# Motherboard.net
KiCad netlist of a schematic drawn in EAGLE
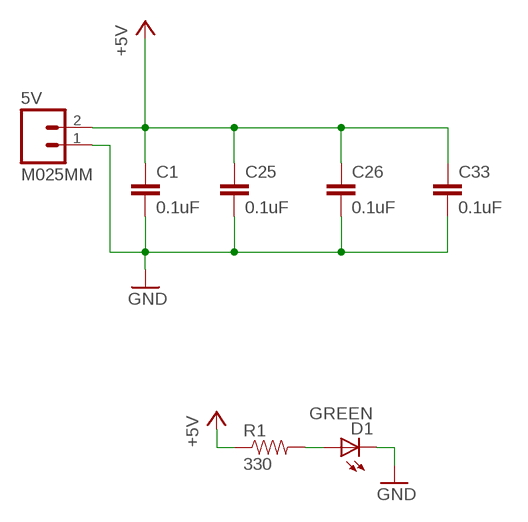
[diagram p0: schematic, sheet 1]
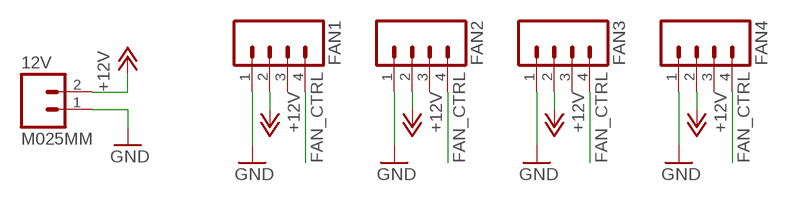
[diagram p1: schematic, sheet 2]
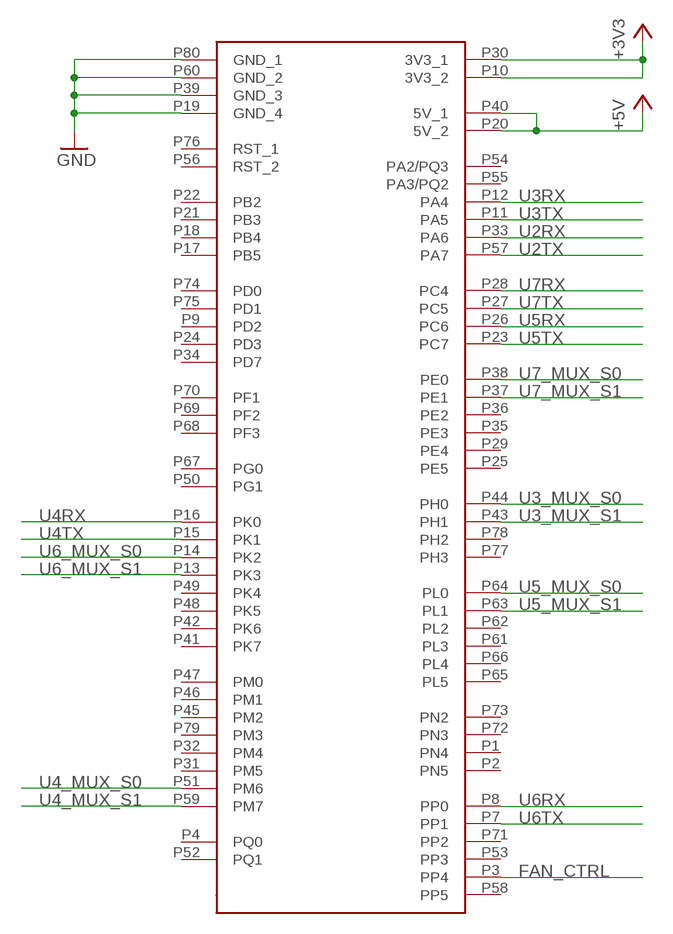
[diagram p2: schematic, sheet 3]
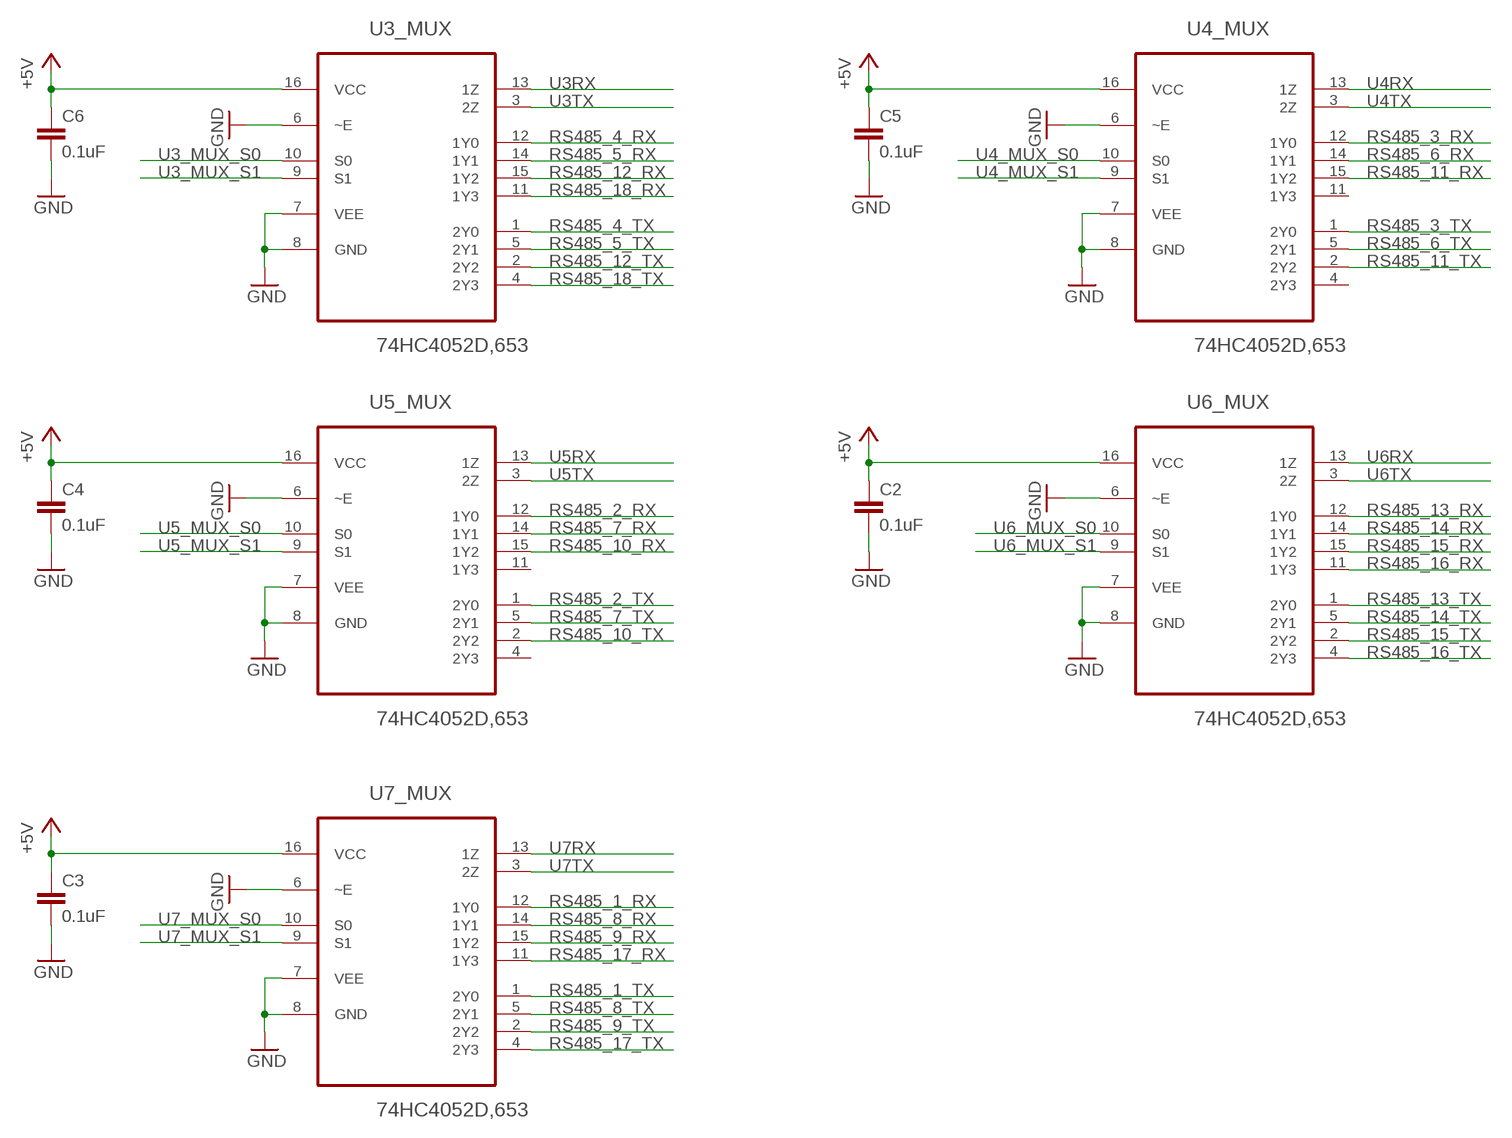
[diagram p3: schematic, sheet 4]
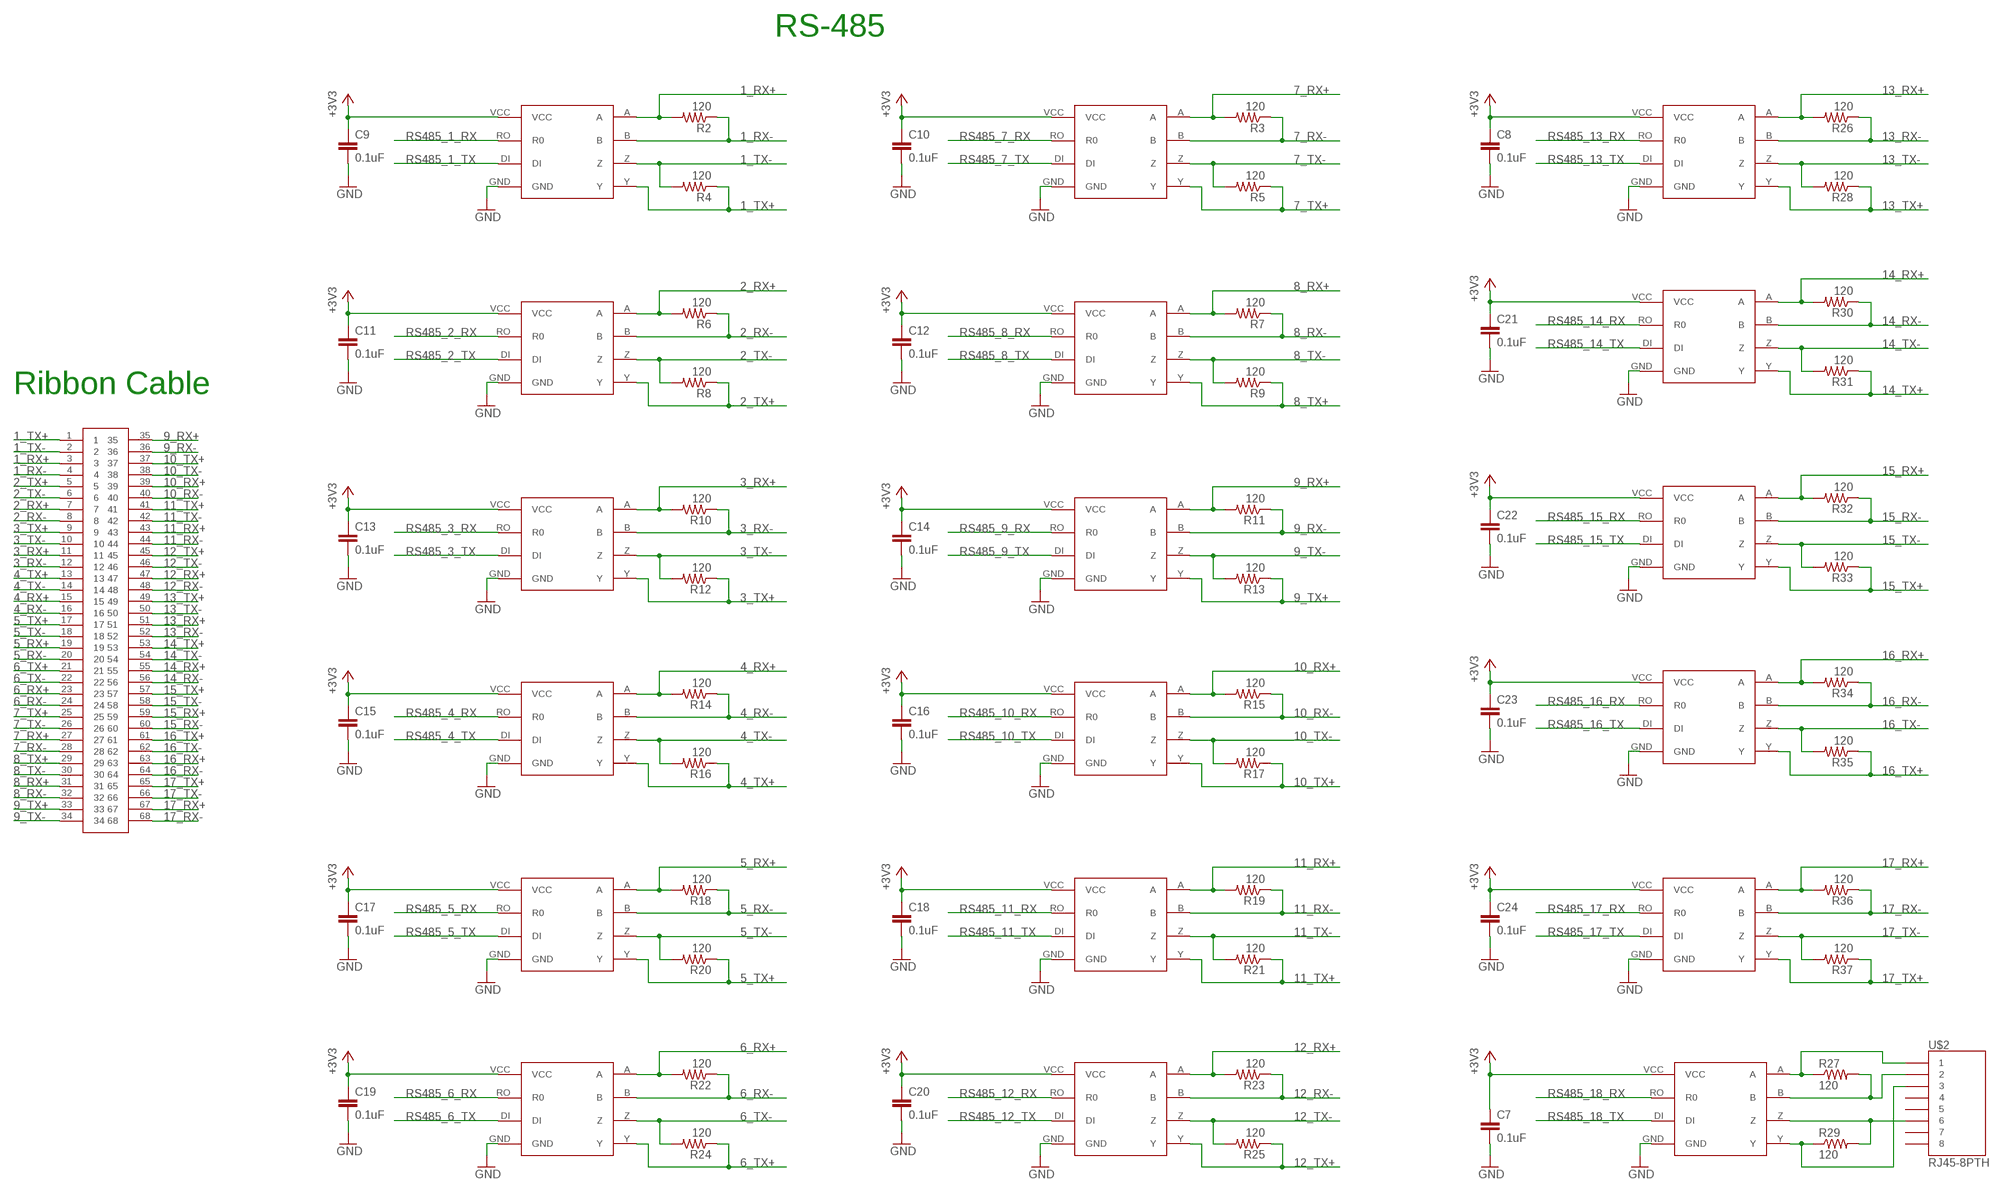
[diagram p4: schematic, sheet 5]
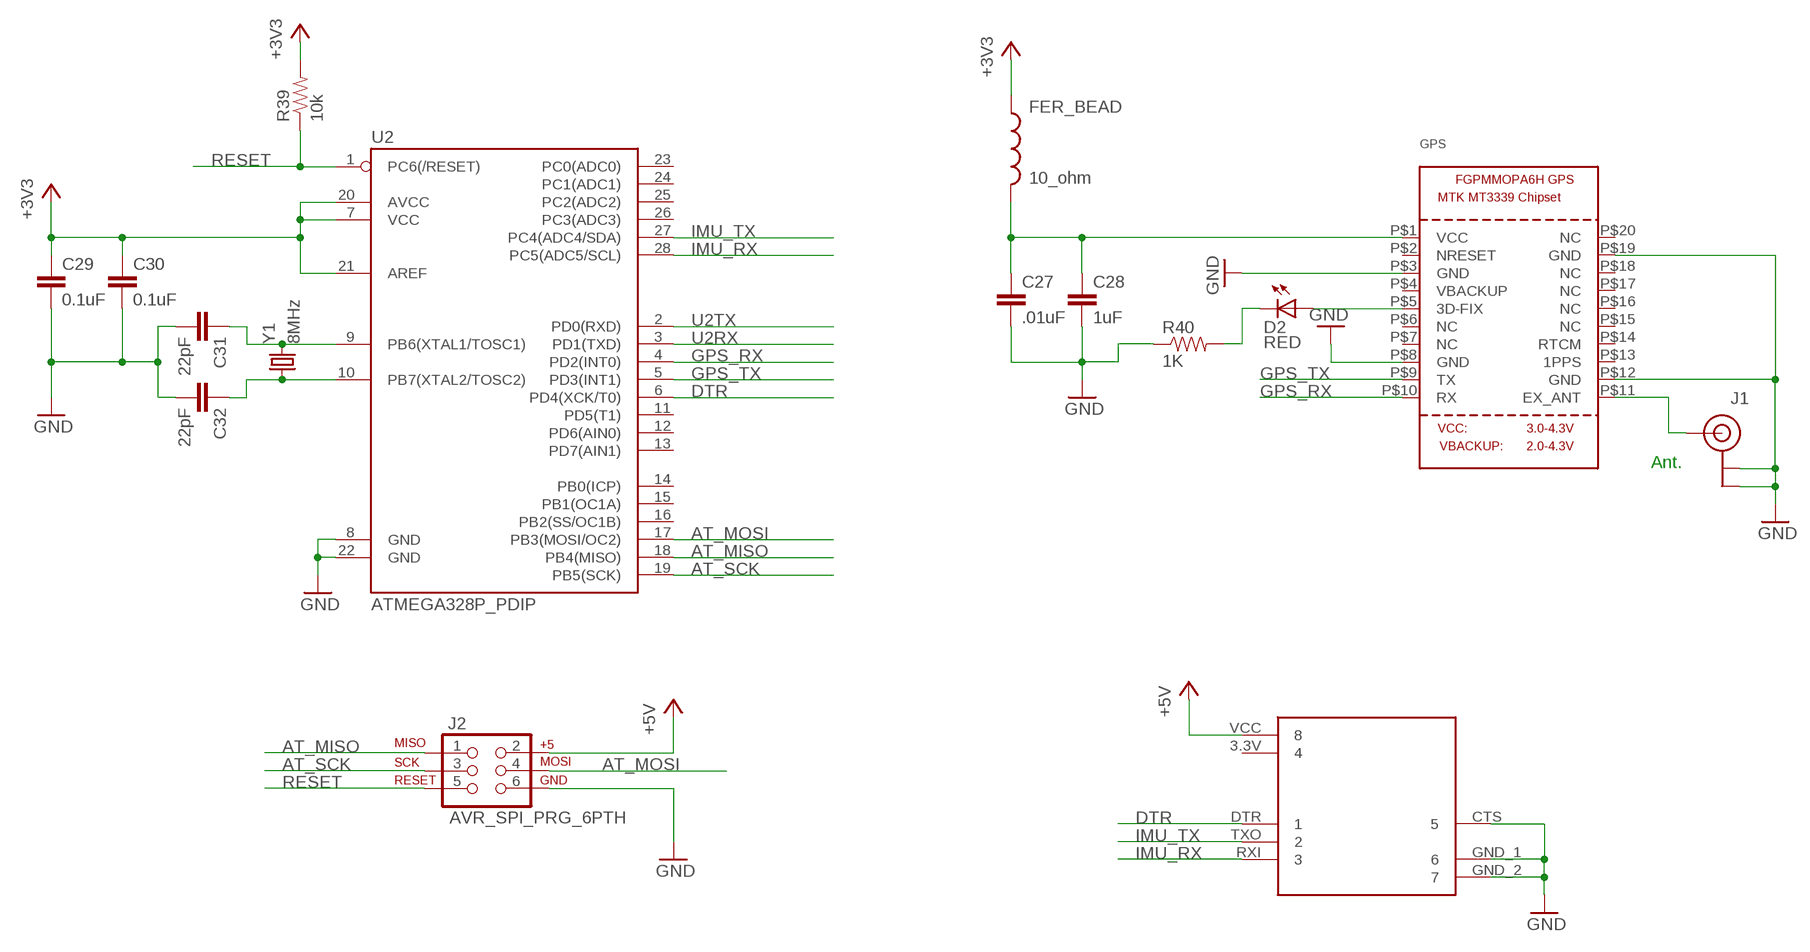
[diagram p5: schematic, sheet 6]
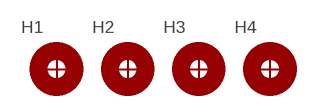
[diagram p6: schematic, sheet 7]

(export (version "E")
  (design (tool "Eeschema 10.0.6"))
  (components
    (comp (ref "C27")
      (value ".01uF")
      (footprint "eagle-import:1206")
      (libsource (lib "eagle-import") (part "CAP1206"))
    )
    (comp (ref "C28")
      (value "1uF")
      (footprint "eagle-import:1206")
      (libsource (lib "eagle-import") (part "CAP1206"))
    )
    (comp (ref "C29")
      (value "0.1uF")
      (footprint "eagle-import:1206")
      (libsource (lib "eagle-import") (part "CAP1206"))
    )
    (comp (ref "C30")
      (value "0.1uF")
      (footprint "eagle-import:1206")
      (libsource (lib "eagle-import") (part "CAP1206"))
    )
    (comp (ref "C31")
      (value "22pF")
      (footprint "eagle-import:1206")
      (libsource (lib "eagle-import") (part "CAP1206"))
    )
    (comp (ref "C32")
      (value "22pF")
      (footprint "eagle-import:1206")
      (libsource (lib "eagle-import") (part "CAP1206"))
    )
    (comp (ref "D2")
      (value "RED")
      (footprint "eagle-import:LED-1206")
      (libsource (lib "eagle-import") (part "LED-RED1206"))
    )
    (comp (ref "FER_BEAD")
      (value "10_ohm")
      (footprint "eagle-import:0603")
      (libsource (lib "eagle-import") (part "INDUCTOR30OHM,1.8A"))
    )
    (comp (ref "GPS")
      (value "GPS_FGPMMOPA6H")
      (footprint "eagle-import:FGPMMOPA6H")
      (libsource (lib "eagle-import") (part "GPS_FGPMMOPA6H"))
    )
    (comp (ref "J1")
      (value "U.FL")
      (footprint "eagle-import:U.FL")
      (libsource (lib "eagle-import") (part "U.FL"))
    )
    (comp (ref "J2")
      (value "AVR_SPI_PRG_6PTH")
      (footprint "eagle-import:2X3")
      (libsource (lib "eagle-import") (part "AVR_SPI_PRG_6PTH"))
    )
    (comp (ref "R39")
      (value "10k")
      (footprint "eagle-import:1206")
      (libsource (lib "eagle-import") (part "SparkFun-Resistors_RESISTOR1206"))
    )
    (comp (ref "R40")
      (value "1K")
      (footprint "eagle-import:1206")
      (libsource (lib "eagle-import") (part "RESISTOR1206"))
    )
    (comp (ref "U$1")
      (value "RAZOR_IMU")
      (footprint "eagle-import:RAZOR_IMU")
      (libsource (lib "eagle-import") (part "RAZOR_IMU"))
    )
    (comp (ref "U2")
      (value "ATMEGA328P_PDIP")
      (footprint "eagle-import:DIL28-3")
      (libsource (lib "eagle-import") (part "ATMEGA328P_PDIP"))
    )
    (comp (ref "Y1")
      (value "8MHz")
      (footprint "eagle-import:HC49US")
      (libsource (lib "eagle-import") (part "CRYSTALHC49US"))
    )
    (comp (ref "5V")
      (value "M025MM")
      (footprint "eagle-import:SCREWTERMINAL-5MM-2")
      (libsource (lib "eagle-import") (part "M025MM"))
    )
    (comp (ref "C1")
      (value "0.1uF")
      (footprint "eagle-import:1206")
      (libsource (lib "eagle-import") (part "CAP1206"))
    )
    (comp (ref "C25")
      (value "0.1uF")
      (footprint "eagle-import:1206")
      (libsource (lib "eagle-import") (part "CAP1206"))
    )
    (comp (ref "C26")
      (value "0.1uF")
      (footprint "eagle-import:1206")
      (libsource (lib "eagle-import") (part "CAP1206"))
    )
    (comp (ref "C33")
      (value "0.1uF")
      (footprint "eagle-import:1206")
      (libsource (lib "eagle-import") (part "CAP1206"))
    )
    (comp (ref "D1")
      (value "GREEN")
      (footprint "eagle-import:LED-1206")
      (libsource (lib "eagle-import") (part "LED-GREENLARGE"))
    )
    (comp (ref "R1")
      (value "330")
      (footprint "eagle-import:1206")
      (libsource (lib "eagle-import") (part "RESISTOR1206"))
    )
    (comp (ref "H1")
      (value "H_MNTHOLE_#4")
      (footprint "eagle-import:H_MNTHOLE_#4")
      (libsource (lib "eagle-import") (part "H_MNTHOLE_#4"))
    )
    (comp (ref "H2")
      (value "H_MNTHOLE_#4")
      (footprint "eagle-import:H_MNTHOLE_#4")
      (libsource (lib "eagle-import") (part "H_MNTHOLE_#4"))
    )
    (comp (ref "H3")
      (value "H_MNTHOLE_#4")
      (footprint "eagle-import:H_MNTHOLE_#4")
      (libsource (lib "eagle-import") (part "H_MNTHOLE_#4"))
    )
    (comp (ref "H4")
      (value "H_MNTHOLE_#4")
      (footprint "eagle-import:H_MNTHOLE_#4")
      (libsource (lib "eagle-import") (part "H_MNTHOLE_#4"))
    )
    (comp (ref "C2")
      (value "0.1uF")
      (footprint "eagle-import:1206")
      (libsource (lib "eagle-import") (part "CAP1206"))
    )
    (comp (ref "C3")
      (value "0.1uF")
      (footprint "eagle-import:1206")
      (libsource (lib "eagle-import") (part "CAP1206"))
    )
    (comp (ref "C4")
      (value "0.1uF")
      (footprint "eagle-import:1206")
      (libsource (lib "eagle-import") (part "CAP1206"))
    )
    (comp (ref "C5")
      (value "0.1uF")
      (footprint "eagle-import:1206")
      (libsource (lib "eagle-import") (part "CAP1206"))
    )
    (comp (ref "C6")
      (value "0.1uF")
      (footprint "eagle-import:1206")
      (libsource (lib "eagle-import") (part "CAP1206"))
    )
    (comp (ref "U3_MUX")
      (value "74HC4052D,653")
      (footprint "eagle-import:SOIC127P600X175-16N")
      (libsource (lib "eagle-import") (part "74HC4052D,653"))
    )
    (comp (ref "U4_MUX")
      (value "74HC4052D,653")
      (footprint "eagle-import:SOIC127P600X175-16N")
      (libsource (lib "eagle-import") (part "74HC4052D,653"))
    )
    (comp (ref "U5_MUX")
      (value "74HC4052D,653")
      (footprint "eagle-import:SOIC127P600X175-16N")
      (libsource (lib "eagle-import") (part "74HC4052D,653"))
    )
    (comp (ref "U6_MUX")
      (value "74HC4052D,653")
      (footprint "eagle-import:SOIC127P600X175-16N")
      (libsource (lib "eagle-import") (part "74HC4052D,653"))
    )
    (comp (ref "U7_MUX")
      (value "74HC4052D,653")
      (footprint "eagle-import:SOIC127P600X175-16N")
      (libsource (lib "eagle-import") (part "74HC4052D,653"))
    )
    (comp (ref "C7")
      (value "0.1uF")
      (footprint "eagle-import:1206")
      (libsource (lib "eagle-import") (part "CAP1206"))
    )
    (comp (ref "C8")
      (value "0.1uF")
      (footprint "eagle-import:1206")
      (libsource (lib "eagle-import") (part "CAP1206"))
    )
    (comp (ref "C9")
      (value "0.1uF")
      (footprint "eagle-import:1206")
      (libsource (lib "eagle-import") (part "CAP1206"))
    )
    (comp (ref "C10")
      (value "0.1uF")
      (footprint "eagle-import:1206")
      (libsource (lib "eagle-import") (part "CAP1206"))
    )
    (comp (ref "C11")
      (value "0.1uF")
      (footprint "eagle-import:1206")
      (libsource (lib "eagle-import") (part "CAP1206"))
    )
    (comp (ref "C12")
      (value "0.1uF")
      (footprint "eagle-import:1206")
      (libsource (lib "eagle-import") (part "CAP1206"))
    )
    (comp (ref "C13")
      (value "0.1uF")
      (footprint "eagle-import:1206")
      (libsource (lib "eagle-import") (part "CAP1206"))
    )
    (comp (ref "C14")
      (value "0.1uF")
      (footprint "eagle-import:1206")
      (libsource (lib "eagle-import") (part "CAP1206"))
    )
    (comp (ref "C15")
      (value "0.1uF")
      (footprint "eagle-import:1206")
      (libsource (lib "eagle-import") (part "CAP1206"))
    )
    (comp (ref "C16")
      (value "0.1uF")
      (footprint "eagle-import:1206")
      (libsource (lib "eagle-import") (part "CAP1206"))
    )
    (comp (ref "C17")
      (value "0.1uF")
      (footprint "eagle-import:1206")
      (libsource (lib "eagle-import") (part "CAP1206"))
    )
    (comp (ref "C18")
      (value "0.1uF")
      (footprint "eagle-import:1206")
      (libsource (lib "eagle-import") (part "CAP1206"))
    )
    (comp (ref "C19")
      (value "0.1uF")
      (footprint "eagle-import:1206")
      (libsource (lib "eagle-import") (part "CAP1206"))
    )
    (comp (ref "C20")
      (value "0.1uF")
      (footprint "eagle-import:1206")
      (libsource (lib "eagle-import") (part "CAP1206"))
    )
    (comp (ref "C21")
      (value "0.1uF")
      (footprint "eagle-import:1206")
      (libsource (lib "eagle-import") (part "CAP1206"))
    )
    (comp (ref "C22")
      (value "0.1uF")
      (footprint "eagle-import:1206")
      (libsource (lib "eagle-import") (part "CAP1206"))
    )
    (comp (ref "C23")
      (value "0.1uF")
      (footprint "eagle-import:1206")
      (libsource (lib "eagle-import") (part "CAP1206"))
    )
    (comp (ref "C24")
      (value "0.1uF")
      (footprint "eagle-import:1206")
      (libsource (lib "eagle-import") (part "CAP1206"))
    )
    (comp (ref "R2")
      (value "120")
      (footprint "eagle-import:1206")
      (libsource (lib "eagle-import") (part "RESISTOR1206"))
    )
    (comp (ref "R3")
      (value "120")
      (footprint "eagle-import:1206")
      (libsource (lib "eagle-import") (part "RESISTOR1206"))
    )
    (comp (ref "R4")
      (value "120")
      (footprint "eagle-import:1206")
      (libsource (lib "eagle-import") (part "RESISTOR1206"))
    )
    (comp (ref "R5")
      (value "120")
      (footprint "eagle-import:1206")
      (libsource (lib "eagle-import") (part "RESISTOR1206"))
    )
    (comp (ref "R6")
      (value "120")
      (footprint "eagle-import:1206")
      (libsource (lib "eagle-import") (part "RESISTOR1206"))
    )
    (comp (ref "R7")
      (value "120")
      (footprint "eagle-import:1206")
      (libsource (lib "eagle-import") (part "RESISTOR1206"))
    )
    (comp (ref "R8")
      (value "120")
      (footprint "eagle-import:1206")
      (libsource (lib "eagle-import") (part "RESISTOR1206"))
    )
    (comp (ref "R9")
      (value "120")
      (footprint "eagle-import:1206")
      (libsource (lib "eagle-import") (part "RESISTOR1206"))
    )
    (comp (ref "R10")
      (value "120")
      (footprint "eagle-import:1206")
      (libsource (lib "eagle-import") (part "RESISTOR1206"))
    )
    (comp (ref "R11")
      (value "120")
      (footprint "eagle-import:1206")
      (libsource (lib "eagle-import") (part "RESISTOR1206"))
    )
    (comp (ref "R12")
      (value "120")
      (footprint "eagle-import:1206")
      (libsource (lib "eagle-import") (part "RESISTOR1206"))
    )
    (comp (ref "R13")
      (value "120")
      (footprint "eagle-import:1206")
      (libsource (lib "eagle-import") (part "RESISTOR1206"))
    )
    (comp (ref "R14")
      (value "120")
      (footprint "eagle-import:1206")
      (libsource (lib "eagle-import") (part "RESISTOR1206"))
    )
    (comp (ref "R15")
      (value "120")
      (footprint "eagle-import:1206")
      (libsource (lib "eagle-import") (part "RESISTOR1206"))
    )
    (comp (ref "R16")
      (value "120")
      (footprint "eagle-import:1206")
      (libsource (lib "eagle-import") (part "RESISTOR1206"))
    )
    (comp (ref "R17")
      (value "120")
      (footprint "eagle-import:1206")
      (libsource (lib "eagle-import") (part "RESISTOR1206"))
    )
    (comp (ref "R18")
      (value "120")
      (footprint "eagle-import:1206")
      (libsource (lib "eagle-import") (part "RESISTOR1206"))
    )
    (comp (ref "R19")
      (value "120")
      (footprint "eagle-import:1206")
      (libsource (lib "eagle-import") (part "RESISTOR1206"))
    )
    (comp (ref "R20")
      (value "120")
      (footprint "eagle-import:1206")
      (libsource (lib "eagle-import") (part "RESISTOR1206"))
    )
    (comp (ref "R21")
      (value "120")
      (footprint "eagle-import:1206")
      (libsource (lib "eagle-import") (part "RESISTOR1206"))
    )
    (comp (ref "R22")
      (value "120")
      (footprint "eagle-import:1206")
      (libsource (lib "eagle-import") (part "RESISTOR1206"))
    )
    (comp (ref "R23")
      (value "120")
      (footprint "eagle-import:1206")
      (libsource (lib "eagle-import") (part "RESISTOR1206"))
    )
    (comp (ref "R24")
      (value "120")
      (footprint "eagle-import:1206")
      (libsource (lib "eagle-import") (part "RESISTOR1206"))
    )
    (comp (ref "R25")
      (value "120")
      (footprint "eagle-import:1206")
      (libsource (lib "eagle-import") (part "RESISTOR1206"))
    )
    (comp (ref "R26")
      (value "120")
      (footprint "eagle-import:1206")
      (libsource (lib "eagle-import") (part "RESISTOR1206"))
    )
    (comp (ref "R27")
      (value "120")
      (footprint "eagle-import:1206")
      (libsource (lib "eagle-import") (part "RESISTOR1206"))
    )
    (comp (ref "R28")
      (value "120")
      (footprint "eagle-import:1206")
      (libsource (lib "eagle-import") (part "RESISTOR1206"))
    )
    (comp (ref "R29")
      (value "120")
      (footprint "eagle-import:1206")
      (libsource (lib "eagle-import") (part "RESISTOR1206"))
    )
    (comp (ref "R30")
      (value "120")
      (footprint "eagle-import:1206")
      (libsource (lib "eagle-import") (part "RESISTOR1206"))
    )
    (comp (ref "R31")
      (value "120")
      (footprint "eagle-import:1206")
      (libsource (lib "eagle-import") (part "RESISTOR1206"))
    )
    (comp (ref "R32")
      (value "120")
      (footprint "eagle-import:1206")
      (libsource (lib "eagle-import") (part "RESISTOR1206"))
    )
    (comp (ref "R33")
      (value "120")
      (footprint "eagle-import:1206")
      (libsource (lib "eagle-import") (part "RESISTOR1206"))
    )
    (comp (ref "R34")
      (value "120")
      (footprint "eagle-import:1206")
      (libsource (lib "eagle-import") (part "RESISTOR1206"))
    )
    (comp (ref "R35")
      (value "120")
      (footprint "eagle-import:1206")
      (libsource (lib "eagle-import") (part "RESISTOR1206"))
    )
    (comp (ref "R36")
      (value "120")
      (footprint "eagle-import:1206")
      (libsource (lib "eagle-import") (part "RESISTOR1206"))
    )
    (comp (ref "R37")
      (value "120")
      (footprint "eagle-import:1206")
      (libsource (lib "eagle-import") (part "RESISTOR1206"))
    )
    (comp (ref "RS-485-2")
      (value "MAX3077")
      (footprint "eagle-import:MAX3070E")
      (libsource (lib "eagle-import") (part "MAX3077"))
    )
    (comp (ref "RS_TRANS_1")
      (value "MAX3077")
      (footprint "eagle-import:MAX3070E")
      (libsource (lib "eagle-import") (part "MAX3077"))
    )
    (comp (ref "RS_TRANS_2")
      (value "MAX3077")
      (footprint "eagle-import:MAX3070E")
      (libsource (lib "eagle-import") (part "MAX3077"))
    )
    (comp (ref "RS_TRANS_3")
      (value "MAX3077")
      (footprint "eagle-import:MAX3070E")
      (libsource (lib "eagle-import") (part "MAX3077"))
    )
    (comp (ref "RS_TRANS_4")
      (value "MAX3077")
      (footprint "eagle-import:MAX3070E")
      (libsource (lib "eagle-import") (part "MAX3077"))
    )
    (comp (ref "RS_TRANS_5")
      (value "MAX3077")
      (footprint "eagle-import:MAX3070E")
      (libsource (lib "eagle-import") (part "MAX3077"))
    )
    (comp (ref "RS_TRANS_6")
      (value "MAX3077")
      (footprint "eagle-import:MAX3070E")
      (libsource (lib "eagle-import") (part "MAX3077"))
    )
    (comp (ref "RS_TRANS_7")
      (value "MAX3077")
      (footprint "eagle-import:MAX3070E")
      (libsource (lib "eagle-import") (part "MAX3077"))
    )
    (comp (ref "RS_TRANS_8")
      (value "MAX3077")
      (footprint "eagle-import:MAX3070E")
      (libsource (lib "eagle-import") (part "MAX3077"))
    )
    (comp (ref "RS_TRANS_9")
      (value "MAX3077")
      (footprint "eagle-import:MAX3070E")
      (libsource (lib "eagle-import") (part "MAX3077"))
    )
    (comp (ref "RS_TRANS_10")
      (value "MAX3077")
      (footprint "eagle-import:MAX3070E")
      (libsource (lib "eagle-import") (part "MAX3077"))
    )
    (comp (ref "RS_TRANS_11")
      (value "MAX3077")
      (footprint "eagle-import:MAX3070E")
      (libsource (lib "eagle-import") (part "MAX3077"))
    )
    (comp (ref "RS_TRANS_12")
      (value "MAX3077")
      (footprint "eagle-import:MAX3070E")
      (libsource (lib "eagle-import") (part "MAX3077"))
    )
    (comp (ref "RS_TRANS_13")
      (value "MAX3077")
      (footprint "eagle-import:MAX3070E")
      (libsource (lib "eagle-import") (part "MAX3077"))
    )
    (comp (ref "RS_TRANS_14")
      (value "MAX3077")
      (footprint "eagle-import:MAX3070E")
      (libsource (lib "eagle-import") (part "MAX3077"))
    )
    (comp (ref "RS_TRANS_15")
      (value "MAX3077")
      (footprint "eagle-import:MAX3070E")
      (libsource (lib "eagle-import") (part "MAX3077"))
    )
    (comp (ref "RS_TRANS_16")
      (value "MAX3077")
      (footprint "eagle-import:MAX3070E")
      (libsource (lib "eagle-import") (part "MAX3077"))
    )
    (comp (ref "RS_TRANS_17")
      (value "MAX3077")
      (footprint "eagle-import:MAX3070E")
      (libsource (lib "eagle-import") (part "MAX3077"))
    )
    (comp (ref "U$2")
      (value "RJ45-8PTH")
      (footprint "eagle-import:RJ45-8")
      (libsource (lib "eagle-import") (part "RJ45-8PTH"))
    )
    (comp (ref "U$4")
      (value "TB60050685100")
      (footprint "eagle-import:60050685100")
      (libsource (lib "eagle-import") (part "TB60050685100"))
    )
    (comp (ref "12V")
      (value "M025MM")
      (footprint "eagle-import:SCREWTERMINAL-5MM-2")
      (libsource (lib "eagle-import") (part "M025MM"))
    )
    (comp (ref "FAN1")
      (value "M04LONGPADS")
      (footprint "eagle-import:1X04_LONGPADS")
      (libsource (lib "eagle-import") (part "M04LONGPADS"))
    )
    (comp (ref "FAN2")
      (value "M04LONGPADS")
      (footprint "eagle-import:1X04_LONGPADS")
      (libsource (lib "eagle-import") (part "M04LONGPADS"))
    )
    (comp (ref "FAN3")
      (value "M04LONGPADS")
      (footprint "eagle-import:1X04_LONGPADS")
      (libsource (lib "eagle-import") (part "M04LONGPADS"))
    )
    (comp (ref "FAN4")
      (value "M04LONGPADS")
      (footprint "eagle-import:1X04_LONGPADS")
      (libsource (lib "eagle-import") (part "M04LONGPADS"))
    )
    (comp (ref "U$5")
      (value "STELLARISLAUNCHPAD_CONNECTED")
      (footprint "eagle-import:STELLARISLAUNCHPAD_CONNECTED")
      (libsource (lib "eagle-import") (part "STELLARISLAUNCHPAD_CONNECTED"))
    )
  )
  (nets
    (net (code "1") (name "+3V3") (class "Default")
      (node (ref "C10") (pin "1") (pinfunction "1_1") (pintype "passive"))
      (node (ref "C11") (pin "1") (pinfunction "1_1") (pintype "passive"))
      (node (ref "C12") (pin "1") (pinfunction "1_1") (pintype "passive"))
      (node (ref "C13") (pin "1") (pinfunction "1_1") (pintype "passive"))
      (node (ref "C14") (pin "1") (pinfunction "1_1") (pintype "passive"))
      (node (ref "C15") (pin "1") (pinfunction "1_1") (pintype "passive"))
      (node (ref "C16") (pin "1") (pinfunction "1_1") (pintype "passive"))
      (node (ref "C17") (pin "1") (pinfunction "1_1") (pintype "passive"))
      (node (ref "C18") (pin "1") (pinfunction "1_1") (pintype "passive"))
      (node (ref "C19") (pin "1") (pinfunction "1_1") (pintype "passive"))
      (node (ref "C20") (pin "1") (pinfunction "1_1") (pintype "passive"))
      (node (ref "C21") (pin "1") (pinfunction "1_1") (pintype "passive"))
      (node (ref "C22") (pin "1") (pinfunction "1_1") (pintype "passive"))
      (node (ref "C23") (pin "1") (pinfunction "1_1") (pintype "passive"))
      (node (ref "C24") (pin "1") (pinfunction "1_1") (pintype "passive"))
      (node (ref "C29") (pin "1") (pinfunction "1_1") (pintype "passive"))
      (node (ref "C30") (pin "1") (pinfunction "1_1") (pintype "passive"))
      (node (ref "C7") (pin "1") (pinfunction "1_1") (pintype "passive"))
      (node (ref "C8") (pin "1") (pinfunction "1_1") (pintype "passive"))
      (node (ref "C9") (pin "1") (pinfunction "1_1") (pintype "passive"))
      (node (ref "FER_BEAD") (pin "1") (pinfunction "1_1") (pintype "passive"))
      (node (ref "R39") (pin "2") (pinfunction "2_2") (pintype "passive"))
      (node (ref "RS-485-2") (pin "VCC") (pinfunction "VCC_VCC") (pintype "bidirectional"))
      (node (ref "RS_TRANS_1") (pin "VCC") (pinfunction "VCC_VCC") (pintype "bidirectional"))
      (node (ref "RS_TRANS_10") (pin "VCC") (pinfunction "VCC_VCC") (pintype "bidirectional"))
      (node (ref "RS_TRANS_11") (pin "VCC") (pinfunction "VCC_VCC") (pintype "bidirectional"))
      (node (ref "RS_TRANS_12") (pin "VCC") (pinfunction "VCC_VCC") (pintype "bidirectional"))
      (node (ref "RS_TRANS_13") (pin "VCC") (pinfunction "VCC_VCC") (pintype "bidirectional"))
      (node (ref "RS_TRANS_14") (pin "VCC") (pinfunction "VCC_VCC") (pintype "bidirectional"))
      (node (ref "RS_TRANS_15") (pin "VCC") (pinfunction "VCC_VCC") (pintype "bidirectional"))
      (node (ref "RS_TRANS_16") (pin "VCC") (pinfunction "VCC_VCC") (pintype "bidirectional"))
      (node (ref "RS_TRANS_17") (pin "VCC") (pinfunction "VCC_VCC") (pintype "bidirectional"))
      (node (ref "RS_TRANS_2") (pin "VCC") (pinfunction "VCC_VCC") (pintype "bidirectional"))
      (node (ref "RS_TRANS_3") (pin "VCC") (pinfunction "VCC_VCC") (pintype "bidirectional"))
      (node (ref "RS_TRANS_4") (pin "VCC") (pinfunction "VCC_VCC") (pintype "bidirectional"))
      (node (ref "RS_TRANS_5") (pin "VCC") (pinfunction "VCC_VCC") (pintype "bidirectional"))
      (node (ref "RS_TRANS_6") (pin "VCC") (pinfunction "VCC_VCC") (pintype "bidirectional"))
      (node (ref "RS_TRANS_7") (pin "VCC") (pinfunction "VCC_VCC") (pintype "bidirectional"))
      (node (ref "RS_TRANS_8") (pin "VCC") (pinfunction "VCC_VCC") (pintype "bidirectional"))
      (node (ref "RS_TRANS_9") (pin "VCC") (pinfunction "VCC_VCC") (pintype "bidirectional"))
      (node (ref "U$5") (pin "P10") (pinfunction "3V3_2_P10") (pintype "bidirectional"))
      (node (ref "U$5") (pin "P30") (pinfunction "3V3_1_P30") (pintype "bidirectional"))
      (node (ref "U2") (pin "20") (pinfunction "AVCC_20") (pintype "bidirectional"))
      (node (ref "U2") (pin "21") (pinfunction "AREF_21") (pintype "bidirectional"))
      (node (ref "U2") (pin "7") (pinfunction "VCC_7") (pintype "bidirectional"))
    )
    (net (code "2") (name "+5V") (class "Default")
      (node (ref "5V") (pin "2") (pinfunction "2_2") (pintype "passive"))
      (node (ref "C1") (pin "1") (pinfunction "1_1") (pintype "passive"))
      (node (ref "C2") (pin "1") (pinfunction "1_1") (pintype "passive"))
      (node (ref "C25") (pin "1") (pinfunction "1_1") (pintype "passive"))
      (node (ref "C26") (pin "1") (pinfunction "1_1") (pintype "passive"))
      (node (ref "C3") (pin "1") (pinfunction "1_1") (pintype "passive"))
      (node (ref "C33") (pin "1") (pinfunction "1_1") (pintype "passive"))
      (node (ref "C4") (pin "1") (pinfunction "1_1") (pintype "passive"))
      (node (ref "C5") (pin "1") (pinfunction "1_1") (pintype "passive"))
      (node (ref "C6") (pin "1") (pinfunction "1_1") (pintype "passive"))
      (node (ref "J2") (pin "2") (pinfunction "2_2") (pintype "passive"))
      (node (ref "R1") (pin "1") (pinfunction "1_1") (pintype "passive"))
      (node (ref "U$1") (pin "VCC") (pinfunction "8_VCC") (pintype "bidirectional"))
      (node (ref "U$5") (pin "P20") (pinfunction "5V_2_P20") (pintype "bidirectional"))
      (node (ref "U$5") (pin "P40") (pinfunction "5V_1_P40") (pintype "bidirectional"))
      (node (ref "U3_MUX") (pin "16") (pinfunction "VCC_16") (pintype "power_in"))
      (node (ref "U4_MUX") (pin "16") (pinfunction "VCC_16") (pintype "power_in"))
      (node (ref "U5_MUX") (pin "16") (pinfunction "VCC_16") (pintype "power_in"))
      (node (ref "U6_MUX") (pin "16") (pinfunction "VCC_16") (pintype "power_in"))
      (node (ref "U7_MUX") (pin "16") (pinfunction "VCC_16") (pintype "power_in"))
    )
    (net (code "3") (name "+12V") (class "Default")
      (node (ref "12V") (pin "2") (pinfunction "2_2") (pintype "passive"))
      (node (ref "FAN1") (pin "2") (pinfunction "2_2") (pintype "passive"))
      (node (ref "FAN2") (pin "2") (pinfunction "2_2") (pintype "passive"))
      (node (ref "FAN3") (pin "2") (pinfunction "2_2") (pintype "passive"))
      (node (ref "FAN4") (pin "2") (pinfunction "2_2") (pintype "passive"))
    )
    (net (code "4") (name "1_RX+") (class "Default")
      (node (ref "R2") (pin "2") (pinfunction "2_2") (pintype "passive"))
      (node (ref "RS_TRANS_1") (pin "A") (pinfunction "A_A") (pintype "bidirectional"))
      (node (ref "U$4") (pin "3") (pinfunction "3_3") (pintype "bidirectional"))
    )
    (net (code "5") (name "1_RX-") (class "Default")
      (node (ref "R2") (pin "1") (pinfunction "1_1") (pintype "passive"))
      (node (ref "RS_TRANS_1") (pin "B") (pinfunction "B_B") (pintype "bidirectional"))
      (node (ref "U$4") (pin "4") (pinfunction "4_4") (pintype "bidirectional"))
    )
    (net (code "6") (name "1_TX+") (class "Default")
      (node (ref "R4") (pin "1") (pinfunction "1_1") (pintype "passive"))
      (node (ref "RS_TRANS_1") (pin "Y") (pinfunction "Y_Y") (pintype "bidirectional"))
      (node (ref "U$4") (pin "1") (pinfunction "1_1") (pintype "bidirectional"))
    )
    (net (code "7") (name "1_TX-") (class "Default")
      (node (ref "R4") (pin "2") (pinfunction "2_2") (pintype "passive"))
      (node (ref "RS_TRANS_1") (pin "Z") (pinfunction "Z_Z") (pintype "bidirectional"))
      (node (ref "U$4") (pin "2") (pinfunction "2_2") (pintype "bidirectional"))
    )
    (net (code "8") (name "2_RX+") (class "Default")
      (node (ref "R6") (pin "2") (pinfunction "2_2") (pintype "passive"))
      (node (ref "RS_TRANS_3") (pin "A") (pinfunction "A_A") (pintype "bidirectional"))
      (node (ref "U$4") (pin "7") (pinfunction "7_7") (pintype "bidirectional"))
    )
    (net (code "9") (name "2_RX-") (class "Default")
      (node (ref "R6") (pin "1") (pinfunction "1_1") (pintype "passive"))
      (node (ref "RS_TRANS_3") (pin "B") (pinfunction "B_B") (pintype "bidirectional"))
      (node (ref "U$4") (pin "8") (pinfunction "8_8") (pintype "bidirectional"))
    )
    (net (code "10") (name "2_TX+") (class "Default")
      (node (ref "R8") (pin "1") (pinfunction "1_1") (pintype "passive"))
      (node (ref "RS_TRANS_3") (pin "Y") (pinfunction "Y_Y") (pintype "bidirectional"))
      (node (ref "U$4") (pin "5") (pinfunction "5_5") (pintype "bidirectional"))
    )
    (net (code "11") (name "2_TX-") (class "Default")
      (node (ref "R8") (pin "2") (pinfunction "2_2") (pintype "passive"))
      (node (ref "RS_TRANS_3") (pin "Z") (pinfunction "Z_Z") (pintype "bidirectional"))
      (node (ref "U$4") (pin "6") (pinfunction "6_6") (pintype "bidirectional"))
    )
    (net (code "12") (name "3_RX+") (class "Default")
      (node (ref "R10") (pin "2") (pinfunction "2_2") (pintype "passive"))
      (node (ref "RS_TRANS_5") (pin "A") (pinfunction "A_A") (pintype "bidirectional"))
      (node (ref "U$4") (pin "11") (pinfunction "11_11") (pintype "bidirectional"))
    )
    (net (code "13") (name "3_RX-") (class "Default")
      (node (ref "R10") (pin "1") (pinfunction "1_1") (pintype "passive"))
      (node (ref "RS_TRANS_5") (pin "B") (pinfunction "B_B") (pintype "bidirectional"))
      (node (ref "U$4") (pin "12") (pinfunction "12_12") (pintype "bidirectional"))
    )
    (net (code "14") (name "3_TX+") (class "Default")
      (node (ref "R12") (pin "1") (pinfunction "1_1") (pintype "passive"))
      (node (ref "RS_TRANS_5") (pin "Y") (pinfunction "Y_Y") (pintype "bidirectional"))
      (node (ref "U$4") (pin "9") (pinfunction "9_9") (pintype "bidirectional"))
    )
    (net (code "15") (name "3_TX-") (class "Default")
      (node (ref "R12") (pin "2") (pinfunction "2_2") (pintype "passive"))
      (node (ref "RS_TRANS_5") (pin "Z") (pinfunction "Z_Z") (pintype "bidirectional"))
      (node (ref "U$4") (pin "10") (pinfunction "10_10") (pintype "bidirectional"))
    )
    (net (code "16") (name "4_RX+") (class "Default")
      (node (ref "R14") (pin "2") (pinfunction "2_2") (pintype "passive"))
      (node (ref "RS_TRANS_7") (pin "A") (pinfunction "A_A") (pintype "bidirectional"))
      (node (ref "U$4") (pin "15") (pinfunction "15_15") (pintype "bidirectional"))
    )
    (net (code "17") (name "4_RX-") (class "Default")
      (node (ref "R14") (pin "1") (pinfunction "1_1") (pintype "passive"))
      (node (ref "RS_TRANS_7") (pin "B") (pinfunction "B_B") (pintype "bidirectional"))
      (node (ref "U$4") (pin "16") (pinfunction "16_16") (pintype "bidirectional"))
    )
    (net (code "18") (name "4_TX+") (class "Default")
      (node (ref "R16") (pin "1") (pinfunction "1_1") (pintype "passive"))
      (node (ref "RS_TRANS_7") (pin "Y") (pinfunction "Y_Y") (pintype "bidirectional"))
      (node (ref "U$4") (pin "13") (pinfunction "13_13") (pintype "bidirectional"))
    )
    (net (code "19") (name "4_TX-") (class "Default")
      (node (ref "R16") (pin "2") (pinfunction "2_2") (pintype "passive"))
      (node (ref "RS_TRANS_7") (pin "Z") (pinfunction "Z_Z") (pintype "bidirectional"))
      (node (ref "U$4") (pin "14") (pinfunction "14_14") (pintype "bidirectional"))
    )
    (net (code "20") (name "5_RX+") (class "Default")
      (node (ref "R18") (pin "2") (pinfunction "2_2") (pintype "passive"))
      (node (ref "RS_TRANS_9") (pin "A") (pinfunction "A_A") (pintype "bidirectional"))
      (node (ref "U$4") (pin "19") (pinfunction "19_19") (pintype "bidirectional"))
    )
    (net (code "21") (name "5_RX-") (class "Default")
      (node (ref "R18") (pin "1") (pinfunction "1_1") (pintype "passive"))
      (node (ref "RS_TRANS_9") (pin "B") (pinfunction "B_B") (pintype "bidirectional"))
      (node (ref "U$4") (pin "20") (pinfunction "20_20") (pintype "bidirectional"))
    )
    (net (code "22") (name "5_TX+") (class "Default")
      (node (ref "R20") (pin "1") (pinfunction "1_1") (pintype "passive"))
      (node (ref "RS_TRANS_9") (pin "Y") (pinfunction "Y_Y") (pintype "bidirectional"))
      (node (ref "U$4") (pin "17") (pinfunction "17_17") (pintype "bidirectional"))
    )
    (net (code "23") (name "5_TX-") (class "Default")
      (node (ref "R20") (pin "2") (pinfunction "2_2") (pintype "passive"))
      (node (ref "RS_TRANS_9") (pin "Z") (pinfunction "Z_Z") (pintype "bidirectional"))
      (node (ref "U$4") (pin "18") (pinfunction "18_18") (pintype "bidirectional"))
    )
    (net (code "24") (name "6_RX+") (class "Default")
      (node (ref "R22") (pin "2") (pinfunction "2_2") (pintype "passive"))
      (node (ref "RS_TRANS_11") (pin "A") (pinfunction "A_A") (pintype "bidirectional"))
      (node (ref "U$4") (pin "23") (pinfunction "23_23") (pintype "bidirectional"))
    )
    (net (code "25") (name "6_RX-") (class "Default")
      (node (ref "R22") (pin "1") (pinfunction "1_1") (pintype "passive"))
      (node (ref "RS_TRANS_11") (pin "B") (pinfunction "B_B") (pintype "bidirectional"))
      (node (ref "U$4") (pin "24") (pinfunction "24_24") (pintype "bidirectional"))
    )
    (net (code "26") (name "6_TX+") (class "Default")
      (node (ref "R24") (pin "1") (pinfunction "1_1") (pintype "passive"))
      (node (ref "RS_TRANS_11") (pin "Y") (pinfunction "Y_Y") (pintype "bidirectional"))
      (node (ref "U$4") (pin "21") (pinfunction "21_21") (pintype "bidirectional"))
    )
    (net (code "27") (name "6_TX-") (class "Default")
      (node (ref "R24") (pin "2") (pinfunction "2_2") (pintype "passive"))
      (node (ref "RS_TRANS_11") (pin "Z") (pinfunction "Z_Z") (pintype "bidirectional"))
      (node (ref "U$4") (pin "22") (pinfunction "22_22") (pintype "bidirectional"))
    )
    (net (code "28") (name "7_RX+") (class "Default")
      (node (ref "R3") (pin "2") (pinfunction "2_2") (pintype "passive"))
      (node (ref "RS_TRANS_2") (pin "A") (pinfunction "A_A") (pintype "bidirectional"))
      (node (ref "U$4") (pin "27") (pinfunction "27_27") (pintype "bidirectional"))
    )
    (net (code "29") (name "7_RX-") (class "Default")
      (node (ref "R3") (pin "1") (pinfunction "1_1") (pintype "passive"))
      (node (ref "RS_TRANS_2") (pin "B") (pinfunction "B_B") (pintype "bidirectional"))
      (node (ref "U$4") (pin "28") (pinfunction "28_28") (pintype "bidirectional"))
    )
    (net (code "30") (name "7_TX+") (class "Default")
      (node (ref "R5") (pin "1") (pinfunction "1_1") (pintype "passive"))
      (node (ref "RS_TRANS_2") (pin "Y") (pinfunction "Y_Y") (pintype "bidirectional"))
      (node (ref "U$4") (pin "25") (pinfunction "25_25") (pintype "bidirectional"))
    )
    (net (code "31") (name "7_TX-") (class "Default")
      (node (ref "R5") (pin "2") (pinfunction "2_2") (pintype "passive"))
      (node (ref "RS_TRANS_2") (pin "Z") (pinfunction "Z_Z") (pintype "bidirectional"))
      (node (ref "U$4") (pin "26") (pinfunction "26_26") (pintype "bidirectional"))
    )
    (net (code "32") (name "8_RX+") (class "Default")
      (node (ref "R7") (pin "2") (pinfunction "2_2") (pintype "passive"))
      (node (ref "RS_TRANS_4") (pin "A") (pinfunction "A_A") (pintype "bidirectional"))
      (node (ref "U$4") (pin "31") (pinfunction "31_31") (pintype "bidirectional"))
    )
    (net (code "33") (name "8_RX-") (class "Default")
      (node (ref "R7") (pin "1") (pinfunction "1_1") (pintype "passive"))
      (node (ref "RS_TRANS_4") (pin "B") (pinfunction "B_B") (pintype "bidirectional"))
      (node (ref "U$4") (pin "32") (pinfunction "32_32") (pintype "bidirectional"))
    )
    (net (code "34") (name "8_TX+") (class "Default")
      (node (ref "R9") (pin "1") (pinfunction "1_1") (pintype "passive"))
      (node (ref "RS_TRANS_4") (pin "Y") (pinfunction "Y_Y") (pintype "bidirectional"))
      (node (ref "U$4") (pin "29") (pinfunction "29_29") (pintype "bidirectional"))
    )
    (net (code "35") (name "8_TX-") (class "Default")
      (node (ref "R9") (pin "2") (pinfunction "2_2") (pintype "passive"))
      (node (ref "RS_TRANS_4") (pin "Z") (pinfunction "Z_Z") (pintype "bidirectional"))
      (node (ref "U$4") (pin "30") (pinfunction "30_30") (pintype "bidirectional"))
    )
    (net (code "36") (name "9_RX+") (class "Default")
      (node (ref "R11") (pin "2") (pinfunction "2_2") (pintype "passive"))
      (node (ref "RS_TRANS_6") (pin "A") (pinfunction "A_A") (pintype "bidirectional"))
      (node (ref "U$4") (pin "35") (pinfunction "35_35") (pintype "bidirectional"))
    )
    (net (code "37") (name "9_RX-") (class "Default")
      (node (ref "R11") (pin "1") (pinfunction "1_1") (pintype "passive"))
      (node (ref "RS_TRANS_6") (pin "B") (pinfunction "B_B") (pintype "bidirectional"))
      (node (ref "U$4") (pin "36") (pinfunction "36_36") (pintype "bidirectional"))
    )
    (net (code "38") (name "9_TX+") (class "Default")
      (node (ref "R13") (pin "1") (pinfunction "1_1") (pintype "passive"))
      (node (ref "RS_TRANS_6") (pin "Y") (pinfunction "Y_Y") (pintype "bidirectional"))
      (node (ref "U$4") (pin "33") (pinfunction "33_33") (pintype "bidirectional"))
    )
    (net (code "39") (name "9_TX-") (class "Default")
      (node (ref "R13") (pin "2") (pinfunction "2_2") (pintype "passive"))
      (node (ref "RS_TRANS_6") (pin "Z") (pinfunction "Z_Z") (pintype "bidirectional"))
      (node (ref "U$4") (pin "34") (pinfunction "34_34") (pintype "bidirectional"))
    )
    (net (code "40") (name "10_RX+") (class "Default")
      (node (ref "R15") (pin "2") (pinfunction "2_2") (pintype "passive"))
      (node (ref "RS_TRANS_8") (pin "A") (pinfunction "A_A") (pintype "bidirectional"))
      (node (ref "U$4") (pin "39") (pinfunction "39_39") (pintype "bidirectional"))
    )
    (net (code "41") (name "10_RX-") (class "Default")
      (node (ref "R15") (pin "1") (pinfunction "1_1") (pintype "passive"))
      (node (ref "RS_TRANS_8") (pin "B") (pinfunction "B_B") (pintype "bidirectional"))
      (node (ref "U$4") (pin "40") (pinfunction "40_40") (pintype "bidirectional"))
    )
    (net (code "42") (name "10_TX+") (class "Default")
      (node (ref "R17") (pin "1") (pinfunction "1_1") (pintype "passive"))
      (node (ref "RS_TRANS_8") (pin "Y") (pinfunction "Y_Y") (pintype "bidirectional"))
      (node (ref "U$4") (pin "37") (pinfunction "37_37") (pintype "bidirectional"))
    )
    (net (code "43") (name "10_TX-") (class "Default")
      (node (ref "R17") (pin "2") (pinfunction "2_2") (pintype "passive"))
      (node (ref "RS_TRANS_8") (pin "Z") (pinfunction "Z_Z") (pintype "bidirectional"))
      (node (ref "U$4") (pin "38") (pinfunction "38_38") (pintype "bidirectional"))
    )
    (net (code "44") (name "11_RX+") (class "Default")
      (node (ref "R19") (pin "2") (pinfunction "2_2") (pintype "passive"))
      (node (ref "RS_TRANS_10") (pin "A") (pinfunction "A_A") (pintype "bidirectional"))
      (node (ref "U$4") (pin "43") (pinfunction "43_43") (pintype "bidirectional"))
    )
    (net (code "45") (name "11_RX-") (class "Default")
      (node (ref "R19") (pin "1") (pinfunction "1_1") (pintype "passive"))
      (node (ref "RS_TRANS_10") (pin "B") (pinfunction "B_B") (pintype "bidirectional"))
      (node (ref "U$4") (pin "44") (pinfunction "44_44") (pintype "bidirectional"))
    )
    (net (code "46") (name "11_TX+") (class "Default")
      (node (ref "R21") (pin "1") (pinfunction "1_1") (pintype "passive"))
      (node (ref "RS_TRANS_10") (pin "Y") (pinfunction "Y_Y") (pintype "bidirectional"))
      (node (ref "U$4") (pin "41") (pinfunction "41_41") (pintype "bidirectional"))
    )
    (net (code "47") (name "11_TX-") (class "Default")
      (node (ref "R21") (pin "2") (pinfunction "2_2") (pintype "passive"))
      (node (ref "RS_TRANS_10") (pin "Z") (pinfunction "Z_Z") (pintype "bidirectional"))
      (node (ref "U$4") (pin "42") (pinfunction "42_42") (pintype "bidirectional"))
    )
    (net (code "48") (name "12_RX+") (class "Default")
      (node (ref "R23") (pin "2") (pinfunction "2_2") (pintype "passive"))
      (node (ref "RS_TRANS_12") (pin "A") (pinfunction "A_A") (pintype "bidirectional"))
      (node (ref "U$4") (pin "47") (pinfunction "47_47") (pintype "bidirectional"))
    )
    (net (code "49") (name "12_RX-") (class "Default")
      (node (ref "R23") (pin "1") (pinfunction "1_1") (pintype "passive"))
      (node (ref "RS_TRANS_12") (pin "B") (pinfunction "B_B") (pintype "bidirectional"))
      (node (ref "U$4") (pin "48") (pinfunction "48_48") (pintype "bidirectional"))
    )
    (net (code "50") (name "12_TX+") (class "Default")
      (node (ref "R25") (pin "1") (pinfunction "1_1") (pintype "passive"))
      (node (ref "RS_TRANS_12") (pin "Y") (pinfunction "Y_Y") (pintype "bidirectional"))
      (node (ref "U$4") (pin "45") (pinfunction "45_45") (pintype "bidirectional"))
    )
    (net (code "51") (name "12_TX-") (class "Default")
      (node (ref "R25") (pin "2") (pinfunction "2_2") (pintype "passive"))
      (node (ref "RS_TRANS_12") (pin "Z") (pinfunction "Z_Z") (pintype "bidirectional"))
      (node (ref "U$4") (pin "46") (pinfunction "46_46") (pintype "bidirectional"))
    )
    (net (code "52") (name "13_RX+") (class "Default")
      (node (ref "R26") (pin "2") (pinfunction "2_2") (pintype "passive"))
      (node (ref "RS_TRANS_13") (pin "A") (pinfunction "A_A") (pintype "bidirectional"))
      (node (ref "U$4") (pin "51") (pinfunction "51_51") (pintype "bidirectional"))
    )
    (net (code "53") (name "13_RX-") (class "Default")
      (node (ref "R26") (pin "1") (pinfunction "1_1") (pintype "passive"))
      (node (ref "RS_TRANS_13") (pin "B") (pinfunction "B_B") (pintype "bidirectional"))
      (node (ref "U$4") (pin "52") (pinfunction "52_52") (pintype "bidirectional"))
    )
    (net (code "54") (name "13_TX+") (class "Default")
      (node (ref "R28") (pin "1") (pinfunction "1_1") (pintype "passive"))
      (node (ref "RS_TRANS_13") (pin "Y") (pinfunction "Y_Y") (pintype "bidirectional"))
      (node (ref "U$4") (pin "49") (pinfunction "49_49") (pintype "bidirectional"))
    )
    (net (code "55") (name "13_TX-") (class "Default")
      (node (ref "R28") (pin "2") (pinfunction "2_2") (pintype "passive"))
      (node (ref "RS_TRANS_13") (pin "Z") (pinfunction "Z_Z") (pintype "bidirectional"))
      (node (ref "U$4") (pin "50") (pinfunction "50_50") (pintype "bidirectional"))
    )
    (net (code "56") (name "14_RX+") (class "Default")
      (node (ref "R30") (pin "2") (pinfunction "2_2") (pintype "passive"))
      (node (ref "RS_TRANS_14") (pin "A") (pinfunction "A_A") (pintype "bidirectional"))
      (node (ref "U$4") (pin "55") (pinfunction "55_55") (pintype "bidirectional"))
    )
    (net (code "57") (name "14_RX-") (class "Default")
      (node (ref "R30") (pin "1") (pinfunction "1_1") (pintype "passive"))
      (node (ref "RS_TRANS_14") (pin "B") (pinfunction "B_B") (pintype "bidirectional"))
      (node (ref "U$4") (pin "56") (pinfunction "56_56") (pintype "bidirectional"))
    )
    (net (code "58") (name "14_TX+") (class "Default")
      (node (ref "R31") (pin "1") (pinfunction "1_1") (pintype "passive"))
      (node (ref "RS_TRANS_14") (pin "Y") (pinfunction "Y_Y") (pintype "bidirectional"))
      (node (ref "U$4") (pin "53") (pinfunction "53_53") (pintype "bidirectional"))
    )
    (net (code "59") (name "14_TX-") (class "Default")
      (node (ref "R31") (pin "2") (pinfunction "2_2") (pintype "passive"))
      (node (ref "RS_TRANS_14") (pin "Z") (pinfunction "Z_Z") (pintype "bidirectional"))
      (node (ref "U$4") (pin "54") (pinfunction "54_54") (pintype "bidirectional"))
    )
    (net (code "60") (name "15_RX+") (class "Default")
      (node (ref "R32") (pin "2") (pinfunction "2_2") (pintype "passive"))
      (node (ref "RS_TRANS_15") (pin "A") (pinfunction "A_A") (pintype "bidirectional"))
      (node (ref "U$4") (pin "59") (pinfunction "59_59") (pintype "bidirectional"))
    )
    (net (code "61") (name "15_RX-") (class "Default")
      (node (ref "R32") (pin "1") (pinfunction "1_1") (pintype "passive"))
      (node (ref "RS_TRANS_15") (pin "B") (pinfunction "B_B") (pintype "bidirectional"))
      (node (ref "U$4") (pin "60") (pinfunction "60_60") (pintype "bidirectional"))
    )
    (net (code "62") (name "15_TX+") (class "Default")
      (node (ref "R33") (pin "1") (pinfunction "1_1") (pintype "passive"))
      (node (ref "RS_TRANS_15") (pin "Y") (pinfunction "Y_Y") (pintype "bidirectional"))
      (node (ref "U$4") (pin "57") (pinfunction "57_57") (pintype "bidirectional"))
    )
    (net (code "63") (name "15_TX-") (class "Default")
      (node (ref "R33") (pin "2") (pinfunction "2_2") (pintype "passive"))
      (node (ref "RS_TRANS_15") (pin "Z") (pinfunction "Z_Z") (pintype "bidirectional"))
      (node (ref "U$4") (pin "58") (pinfunction "58_58") (pintype "bidirectional"))
    )
    (net (code "64") (name "16_RX+") (class "Default")
      (node (ref "R34") (pin "2") (pinfunction "2_2") (pintype "passive"))
      (node (ref "RS_TRANS_16") (pin "A") (pinfunction "A_A") (pintype "bidirectional"))
      (node (ref "U$4") (pin "63") (pinfunction "63_63") (pintype "bidirectional"))
    )
    (net (code "65") (name "16_RX-") (class "Default")
      (node (ref "R34") (pin "1") (pinfunction "1_1") (pintype "passive"))
      (node (ref "RS_TRANS_16") (pin "B") (pinfunction "B_B") (pintype "bidirectional"))
      (node (ref "U$4") (pin "64") (pinfunction "64_64") (pintype "bidirectional"))
    )
    (net (code "66") (name "16_TX+") (class "Default")
      (node (ref "R35") (pin "1") (pinfunction "1_1") (pintype "passive"))
      (node (ref "RS_TRANS_16") (pin "Y") (pinfunction "Y_Y") (pintype "bidirectional"))
      (node (ref "U$4") (pin "61") (pinfunction "61_61") (pintype "bidirectional"))
    )
    (net (code "67") (name "16_TX-") (class "Default")
      (node (ref "R35") (pin "2") (pinfunction "2_2") (pintype "passive"))
      (node (ref "RS_TRANS_16") (pin "Z") (pinfunction "Z_Z") (pintype "bidirectional"))
      (node (ref "U$4") (pin "62") (pinfunction "62_62") (pintype "bidirectional"))
    )
    (net (code "68") (name "17_RX+") (class "Default")
      (node (ref "R36") (pin "2") (pinfunction "2_2") (pintype "passive"))
      (node (ref "RS_TRANS_17") (pin "A") (pinfunction "A_A") (pintype "bidirectional"))
      (node (ref "U$4") (pin "67") (pinfunction "67_67") (pintype "bidirectional"))
    )
    (net (code "69") (name "17_RX-") (class "Default")
      (node (ref "R36") (pin "1") (pinfunction "1_1") (pintype "passive"))
      (node (ref "RS_TRANS_17") (pin "B") (pinfunction "B_B") (pintype "bidirectional"))
      (node (ref "U$4") (pin "68") (pinfunction "68_68") (pintype "bidirectional"))
    )
    (net (code "70") (name "17_TX+") (class "Default")
      (node (ref "R37") (pin "1") (pinfunction "1_1") (pintype "passive"))
      (node (ref "RS_TRANS_17") (pin "Y") (pinfunction "Y_Y") (pintype "bidirectional"))
      (node (ref "U$4") (pin "65") (pinfunction "65_65") (pintype "bidirectional"))
    )
    (net (code "71") (name "17_TX-") (class "Default")
      (node (ref "R37") (pin "2") (pinfunction "2_2") (pintype "passive"))
      (node (ref "RS_TRANS_17") (pin "Z") (pinfunction "Z_Z") (pintype "bidirectional"))
      (node (ref "U$4") (pin "66") (pinfunction "66_66") (pintype "bidirectional"))
    )
    (net (code "72") (name "AT_MISO") (class "Default")
      (node (ref "J2") (pin "1") (pinfunction "1_1") (pintype "passive"))
      (node (ref "U2") (pin "18") (pinfunction "PB4(MISO)_18") (pintype "bidirectional"))
    )
    (net (code "73") (name "AT_MOSI") (class "Default")
      (node (ref "J2") (pin "4") (pinfunction "4_4") (pintype "passive"))
      (node (ref "U2") (pin "17") (pinfunction "PB3(MOSI/OC2)_17") (pintype "bidirectional"))
    )
    (net (code "74") (name "AT_SCK") (class "Default")
      (node (ref "J2") (pin "3") (pinfunction "3_3") (pintype "passive"))
      (node (ref "U2") (pin "19") (pinfunction "PB5(SCK)_19") (pintype "bidirectional"))
    )
    (net (code "75") (name "DTR") (class "Default")
      (node (ref "U$1") (pin "DTR") (pinfunction "1_DTR") (pintype "bidirectional"))
      (node (ref "U2") (pin "6") (pinfunction "PD4(XCK/T0)_6") (pintype "bidirectional"))
    )
    (net (code "76") (name "FAN_CTRL") (class "Default")
      (node (ref "FAN1") (pin "4") (pinfunction "4_4") (pintype "passive"))
      (node (ref "FAN2") (pin "4") (pinfunction "4_4") (pintype "passive"))
      (node (ref "FAN3") (pin "4") (pinfunction "4_4") (pintype "passive"))
      (node (ref "FAN4") (pin "4") (pinfunction "4_4") (pintype "passive"))
      (node (ref "U$5") (pin "P3") (pinfunction "PP4_P3") (pintype "bidirectional"))
    )
    (net (code "77") (name "GND") (class "Default")
      (node (ref "12V") (pin "1") (pinfunction "1_1") (pintype "passive"))
      (node (ref "5V") (pin "1") (pinfunction "1_1") (pintype "passive"))
      (node (ref "C1") (pin "2") (pinfunction "2_2") (pintype "passive"))
      (node (ref "C10") (pin "2") (pinfunction "2_2") (pintype "passive"))
      (node (ref "C11") (pin "2") (pinfunction "2_2") (pintype "passive"))
      (node (ref "C12") (pin "2") (pinfunction "2_2") (pintype "passive"))
      (node (ref "C13") (pin "2") (pinfunction "2_2") (pintype "passive"))
      (node (ref "C14") (pin "2") (pinfunction "2_2") (pintype "passive"))
      (node (ref "C15") (pin "2") (pinfunction "2_2") (pintype "passive"))
      (node (ref "C16") (pin "2") (pinfunction "2_2") (pintype "passive"))
      (node (ref "C17") (pin "2") (pinfunction "2_2") (pintype "passive"))
      (node (ref "C18") (pin "2") (pinfunction "2_2") (pintype "passive"))
      (node (ref "C19") (pin "2") (pinfunction "2_2") (pintype "passive"))
      (node (ref "C2") (pin "2") (pinfunction "2_2") (pintype "passive"))
      (node (ref "C20") (pin "2") (pinfunction "2_2") (pintype "passive"))
      (node (ref "C21") (pin "2") (pinfunction "2_2") (pintype "passive"))
      (node (ref "C22") (pin "2") (pinfunction "2_2") (pintype "passive"))
      (node (ref "C23") (pin "2") (pinfunction "2_2") (pintype "passive"))
      (node (ref "C24") (pin "2") (pinfunction "2_2") (pintype "passive"))
      (node (ref "C25") (pin "2") (pinfunction "2_2") (pintype "passive"))
      (node (ref "C26") (pin "2") (pinfunction "2_2") (pintype "passive"))
      (node (ref "C27") (pin "2") (pinfunction "2_2") (pintype "passive"))
      (node (ref "C28") (pin "2") (pinfunction "2_2") (pintype "passive"))
      (node (ref "C29") (pin "2") (pinfunction "2_2") (pintype "passive"))
      (node (ref "C3") (pin "2") (pinfunction "2_2") (pintype "passive"))
      (node (ref "C30") (pin "2") (pinfunction "2_2") (pintype "passive"))
      (node (ref "C31") (pin "2") (pinfunction "2_2") (pintype "passive"))
      (node (ref "C32") (pin "2") (pinfunction "2_2") (pintype "passive"))
      (node (ref "C33") (pin "2") (pinfunction "2_2") (pintype "passive"))
      (node (ref "C4") (pin "2") (pinfunction "2_2") (pintype "passive"))
      (node (ref "C5") (pin "2") (pinfunction "2_2") (pintype "passive"))
      (node (ref "C6") (pin "2") (pinfunction "2_2") (pintype "passive"))
      (node (ref "C7") (pin "2") (pinfunction "2_2") (pintype "passive"))
      (node (ref "C8") (pin "2") (pinfunction "2_2") (pintype "passive"))
      (node (ref "C9") (pin "2") (pinfunction "2_2") (pintype "passive"))
      (node (ref "D1") (pin "C") (pinfunction "C_C") (pintype "passive"))
      (node (ref "FAN1") (pin "1") (pinfunction "1_1") (pintype "passive"))
      (node (ref "FAN2") (pin "1") (pinfunction "1_1") (pintype "passive"))
      (node (ref "FAN3") (pin "1") (pinfunction "1_1") (pintype "passive"))
      (node (ref "FAN4") (pin "1") (pinfunction "1_1") (pintype "passive"))
      (node (ref "GPS") (pin "P$12") (pinfunction "GND_P$12") (pintype "bidirectional"))
      (node (ref "GPS") (pin "P$19") (pinfunction "GND_P$19") (pintype "bidirectional"))
      (node (ref "GPS") (pin "P$3") (pinfunction "GND_P$3") (pintype "bidirectional"))
      (node (ref "GPS") (pin "P$8") (pinfunction "GND_P$8") (pintype "bidirectional"))
      (node (ref "J1") (pin "P$1") (pinfunction "GND_P$1") (pintype "bidirectional"))
      (node (ref "J1") (pin "P$2") (pinfunction "GND_P$2") (pintype "bidirectional"))
      (node (ref "J2") (pin "6") (pinfunction "6_6") (pintype "passive"))
      (node (ref "R40") (pin "1") (pinfunction "1_1") (pintype "passive"))
      (node (ref "RS-485-2") (pin "GND") (pinfunction "GND_GND") (pintype "bidirectional"))
      (node (ref "RS_TRANS_1") (pin "GND") (pinfunction "GND_GND") (pintype "bidirectional"))
      (node (ref "RS_TRANS_10") (pin "GND") (pinfunction "GND_GND") (pintype "bidirectional"))
      (node (ref "RS_TRANS_11") (pin "GND") (pinfunction "GND_GND") (pintype "bidirectional"))
      (node (ref "RS_TRANS_12") (pin "GND") (pinfunction "GND_GND") (pintype "bidirectional"))
      (node (ref "RS_TRANS_13") (pin "GND") (pinfunction "GND_GND") (pintype "bidirectional"))
      (node (ref "RS_TRANS_14") (pin "GND") (pinfunction "GND_GND") (pintype "bidirectional"))
      (node (ref "RS_TRANS_15") (pin "GND") (pinfunction "GND_GND") (pintype "bidirectional"))
      (node (ref "RS_TRANS_16") (pin "GND") (pinfunction "GND_GND") (pintype "bidirectional"))
      (node (ref "RS_TRANS_17") (pin "GND") (pinfunction "GND_GND") (pintype "bidirectional"))
      (node (ref "RS_TRANS_2") (pin "GND") (pinfunction "GND_GND") (pintype "bidirectional"))
      (node (ref "RS_TRANS_3") (pin "GND") (pinfunction "GND_GND") (pintype "bidirectional"))
      (node (ref "RS_TRANS_4") (pin "GND") (pinfunction "GND_GND") (pintype "bidirectional"))
      (node (ref "RS_TRANS_5") (pin "GND") (pinfunction "GND_GND") (pintype "bidirectional"))
      (node (ref "RS_TRANS_6") (pin "GND") (pinfunction "GND_GND") (pintype "bidirectional"))
      (node (ref "RS_TRANS_7") (pin "GND") (pinfunction "GND_GND") (pintype "bidirectional"))
      (node (ref "RS_TRANS_8") (pin "GND") (pinfunction "GND_GND") (pintype "bidirectional"))
      (node (ref "RS_TRANS_9") (pin "GND") (pinfunction "GND_GND") (pintype "bidirectional"))
      (node (ref "U$1") (pin "CTS") (pinfunction "5_CTS") (pintype "bidirectional"))
      (node (ref "U$1") (pin "GND_1") (pinfunction "6_GND_1") (pintype "bidirectional"))
      (node (ref "U$1") (pin "GND_2") (pinfunction "7_GND_2") (pintype "bidirectional"))
      (node (ref "U$5") (pin "P19") (pinfunction "GND_4_P19") (pintype "bidirectional"))
      (node (ref "U$5") (pin "P39") (pinfunction "GND_3_P39") (pintype "bidirectional"))
      (node (ref "U$5") (pin "P60") (pinfunction "GND_2_P60") (pintype "bidirectional"))
      (node (ref "U$5") (pin "P80") (pinfunction "GND_1_P80") (pintype "bidirectional"))
      (node (ref "U2") (pin "22") (pinfunction "GND_22") (pintype "bidirectional"))
      (node (ref "U2") (pin "8") (pinfunction "GND_8") (pintype "bidirectional"))
      (node (ref "U3_MUX") (pin "6") (pinfunction "~{E}_6") (pintype "input"))
      (node (ref "U3_MUX") (pin "7") (pinfunction "VEE_7") (pintype "power_in"))
      (node (ref "U3_MUX") (pin "8") (pinfunction "GND_8") (pintype "passive"))
      (node (ref "U4_MUX") (pin "6") (pinfunction "~{E}_6") (pintype "input"))
      (node (ref "U4_MUX") (pin "7") (pinfunction "VEE_7") (pintype "power_in"))
      (node (ref "U4_MUX") (pin "8") (pinfunction "GND_8") (pintype "passive"))
      (node (ref "U5_MUX") (pin "6") (pinfunction "~{E}_6") (pintype "input"))
      (node (ref "U5_MUX") (pin "7") (pinfunction "VEE_7") (pintype "power_in"))
      (node (ref "U5_MUX") (pin "8") (pinfunction "GND_8") (pintype "passive"))
      (node (ref "U6_MUX") (pin "6") (pinfunction "~{E}_6") (pintype "input"))
      (node (ref "U6_MUX") (pin "7") (pinfunction "VEE_7") (pintype "power_in"))
      (node (ref "U6_MUX") (pin "8") (pinfunction "GND_8") (pintype "passive"))
      (node (ref "U7_MUX") (pin "6") (pinfunction "~{E}_6") (pintype "input"))
      (node (ref "U7_MUX") (pin "7") (pinfunction "VEE_7") (pintype "power_in"))
      (node (ref "U7_MUX") (pin "8") (pinfunction "GND_8") (pintype "passive"))
    )
    (net (code "78") (name "GPS_RX") (class "Default")
      (node (ref "GPS") (pin "P$10") (pinfunction "RX_P$10") (pintype "bidirectional"))
      (node (ref "U2") (pin "4") (pinfunction "PD2(INT0)_4") (pintype "bidirectional"))
    )
    (net (code "79") (name "GPS_TX") (class "Default")
      (node (ref "GPS") (pin "P$9") (pinfunction "TX_P$9") (pintype "bidirectional"))
      (node (ref "U2") (pin "5") (pinfunction "PD3(INT1)_5") (pintype "bidirectional"))
    )
    (net (code "80") (name "IMU_RX") (class "Default")
      (node (ref "U$1") (pin "RXI") (pinfunction "3_RXI") (pintype "bidirectional"))
      (node (ref "U2") (pin "28") (pinfunction "PC5(ADC5/SCL)_28") (pintype "bidirectional"))
    )
    (net (code "81") (name "IMU_TX") (class "Default")
      (node (ref "U$1") (pin "TXO") (pinfunction "2_TXO") (pintype "bidirectional"))
      (node (ref "U2") (pin "27") (pinfunction "PC4(ADC4/SDA)_27") (pintype "bidirectional"))
    )
    (net (code "82") (name "Net-(D1-PadA)") (class "Default")
      (node (ref "D1") (pin "A") (pinfunction "A_A") (pintype "passive"))
      (node (ref "R1") (pin "2") (pinfunction "2_2") (pintype "passive"))
    )
    (net (code "83") (name "Net-(D2-PadC)") (class "Default")
      (node (ref "D2") (pin "C") (pinfunction "C_C") (pintype "passive"))
      (node (ref "R40") (pin "2") (pinfunction "2_2") (pintype "passive"))
    )
    (net (code "84") (name "Net-(GPS-3D-FIX)") (class "Default")
      (node (ref "D2") (pin "A") (pinfunction "A_A") (pintype "passive"))
      (node (ref "GPS") (pin "P$5") (pinfunction "3D-FIX_P$5") (pintype "bidirectional"))
    )
    (net (code "85") (name "Net-(GPS-EX_ANT)") (class "Default")
      (node (ref "GPS") (pin "P$11") (pinfunction "EX_ANT_P$11") (pintype "bidirectional"))
      (node (ref "J1") (pin "P$3") (pinfunction "SIGNAL_P$3") (pintype "bidirectional"))
    )
    (net (code "86") (name "Net-(GPS-VCC)") (class "Default")
      (node (ref "C27") (pin "1") (pinfunction "1_1") (pintype "passive"))
      (node (ref "C28") (pin "1") (pinfunction "1_1") (pintype "passive"))
      (node (ref "FER_BEAD") (pin "2") (pinfunction "2_2") (pintype "passive"))
      (node (ref "GPS") (pin "P$1") (pinfunction "VCC_P$1") (pintype "bidirectional"))
    )
    (net (code "87") (name "Net-(R27-Pad1)") (class "Default")
      (node (ref "R27") (pin "1") (pinfunction "1_1") (pintype "passive"))
      (node (ref "RS-485-2") (pin "A") (pinfunction "A_A") (pintype "bidirectional"))
      (node (ref "U$2") (pin "1") (pinfunction "1_1") (pintype "bidirectional"))
    )
    (net (code "88") (name "Net-(R27-Pad2)") (class "Default")
      (node (ref "R27") (pin "2") (pinfunction "2_2") (pintype "passive"))
      (node (ref "RS-485-2") (pin "B") (pinfunction "B_B") (pintype "bidirectional"))
      (node (ref "U$2") (pin "2") (pinfunction "2_2") (pintype "bidirectional"))
    )
    (net (code "89") (name "Net-(R29-Pad1)") (class "Default")
      (node (ref "R29") (pin "1") (pinfunction "1_1") (pintype "passive"))
      (node (ref "RS-485-2") (pin "Y") (pinfunction "Y_Y") (pintype "bidirectional"))
      (node (ref "U$2") (pin "3") (pinfunction "3_3") (pintype "bidirectional"))
    )
    (net (code "90") (name "Net-(R29-Pad2)") (class "Default")
      (node (ref "R29") (pin "2") (pinfunction "2_2") (pintype "passive"))
      (node (ref "RS-485-2") (pin "Z") (pinfunction "Z_Z") (pintype "bidirectional"))
      (node (ref "U$2") (pin "6") (pinfunction "6_6") (pintype "bidirectional"))
    )
    (net (code "91") (name "Net-(U2-PB6(XTAL1{slash}TOSC1))") (class "Default")
      (node (ref "C31") (pin "1") (pinfunction "1_1") (pintype "passive"))
      (node (ref "U2") (pin "9") (pinfunction "PB6(XTAL1/TOSC1)_9") (pintype "bidirectional"))
      (node (ref "Y1") (pin "2") (pinfunction "2_2") (pintype "passive"))
    )
    (net (code "92") (name "Net-(U2-PB7(XTAL2{slash}TOSC2))") (class "Default")
      (node (ref "C32") (pin "1") (pinfunction "1_1") (pintype "passive"))
      (node (ref "U2") (pin "10") (pinfunction "PB7(XTAL2/TOSC2)_10") (pintype "bidirectional"))
      (node (ref "Y1") (pin "1") (pinfunction "1_1") (pintype "passive"))
    )
    (net (code "93") (name "RESET") (class "Default")
      (node (ref "J2") (pin "5") (pinfunction "5_5") (pintype "passive"))
      (node (ref "R39") (pin "1") (pinfunction "1_1") (pintype "passive"))
      (node (ref "U2") (pin "1") (pinfunction "PC6(/RESET)_1") (pintype "bidirectional"))
    )
    (net (code "94") (name "RS485_1_RX") (class "Default")
      (node (ref "RS_TRANS_1") (pin "RO") (pinfunction "R0_RO") (pintype "bidirectional"))
      (node (ref "U7_MUX") (pin "12") (pinfunction "1Y0_12") (pintype "bidirectional"))
    )
    (net (code "95") (name "RS485_1_TX") (class "Default")
      (node (ref "RS_TRANS_1") (pin "DI") (pinfunction "DI_DI") (pintype "bidirectional"))
      (node (ref "U7_MUX") (pin "1") (pinfunction "2Y0_1") (pintype "bidirectional"))
    )
    (net (code "96") (name "RS485_2_RX") (class "Default")
      (node (ref "RS_TRANS_3") (pin "RO") (pinfunction "R0_RO") (pintype "bidirectional"))
      (node (ref "U5_MUX") (pin "12") (pinfunction "1Y0_12") (pintype "bidirectional"))
    )
    (net (code "97") (name "RS485_2_TX") (class "Default")
      (node (ref "RS_TRANS_3") (pin "DI") (pinfunction "DI_DI") (pintype "bidirectional"))
      (node (ref "U5_MUX") (pin "1") (pinfunction "2Y0_1") (pintype "bidirectional"))
    )
    (net (code "98") (name "RS485_3_RX") (class "Default")
      (node (ref "RS_TRANS_5") (pin "RO") (pinfunction "R0_RO") (pintype "bidirectional"))
      (node (ref "U4_MUX") (pin "12") (pinfunction "1Y0_12") (pintype "bidirectional"))
    )
    (net (code "99") (name "RS485_3_TX") (class "Default")
      (node (ref "RS_TRANS_5") (pin "DI") (pinfunction "DI_DI") (pintype "bidirectional"))
      (node (ref "U4_MUX") (pin "1") (pinfunction "2Y0_1") (pintype "bidirectional"))
    )
    (net (code "100") (name "RS485_4_RX") (class "Default")
      (node (ref "RS_TRANS_7") (pin "RO") (pinfunction "R0_RO") (pintype "bidirectional"))
      (node (ref "U3_MUX") (pin "12") (pinfunction "1Y0_12") (pintype "bidirectional"))
    )
    (net (code "101") (name "RS485_4_TX") (class "Default")
      (node (ref "RS_TRANS_7") (pin "DI") (pinfunction "DI_DI") (pintype "bidirectional"))
      (node (ref "U3_MUX") (pin "1") (pinfunction "2Y0_1") (pintype "bidirectional"))
    )
    (net (code "102") (name "RS485_5_RX") (class "Default")
      (node (ref "RS_TRANS_9") (pin "RO") (pinfunction "R0_RO") (pintype "bidirectional"))
      (node (ref "U3_MUX") (pin "14") (pinfunction "1Y1_14") (pintype "bidirectional"))
    )
    (net (code "103") (name "RS485_5_TX") (class "Default")
      (node (ref "RS_TRANS_9") (pin "DI") (pinfunction "DI_DI") (pintype "bidirectional"))
      (node (ref "U3_MUX") (pin "5") (pinfunction "2Y1_5") (pintype "bidirectional"))
    )
    (net (code "104") (name "RS485_6_RX") (class "Default")
      (node (ref "RS_TRANS_11") (pin "RO") (pinfunction "R0_RO") (pintype "bidirectional"))
      (node (ref "U4_MUX") (pin "14") (pinfunction "1Y1_14") (pintype "bidirectional"))
    )
    (net (code "105") (name "RS485_6_TX") (class "Default")
      (node (ref "RS_TRANS_11") (pin "DI") (pinfunction "DI_DI") (pintype "bidirectional"))
      (node (ref "U4_MUX") (pin "5") (pinfunction "2Y1_5") (pintype "bidirectional"))
    )
    (net (code "106") (name "RS485_7_RX") (class "Default")
      (node (ref "RS_TRANS_2") (pin "RO") (pinfunction "R0_RO") (pintype "bidirectional"))
      (node (ref "U5_MUX") (pin "14") (pinfunction "1Y1_14") (pintype "bidirectional"))
    )
    (net (code "107") (name "RS485_7_TX") (class "Default")
      (node (ref "RS_TRANS_2") (pin "DI") (pinfunction "DI_DI") (pintype "bidirectional"))
      (node (ref "U5_MUX") (pin "5") (pinfunction "2Y1_5") (pintype "bidirectional"))
    )
    (net (code "108") (name "RS485_8_RX") (class "Default")
      (node (ref "RS_TRANS_4") (pin "RO") (pinfunction "R0_RO") (pintype "bidirectional"))
      (node (ref "U7_MUX") (pin "14") (pinfunction "1Y1_14") (pintype "bidirectional"))
    )
    (net (code "109") (name "RS485_8_TX") (class "Default")
      (node (ref "RS_TRANS_4") (pin "DI") (pinfunction "DI_DI") (pintype "bidirectional"))
      (node (ref "U7_MUX") (pin "5") (pinfunction "2Y1_5") (pintype "bidirectional"))
    )
    (net (code "110") (name "RS485_9_RX") (class "Default")
      (node (ref "RS_TRANS_6") (pin "RO") (pinfunction "R0_RO") (pintype "bidirectional"))
      (node (ref "U7_MUX") (pin "15") (pinfunction "1Y2_15") (pintype "bidirectional"))
    )
    (net (code "111") (name "RS485_9_TX") (class "Default")
      (node (ref "RS_TRANS_6") (pin "DI") (pinfunction "DI_DI") (pintype "bidirectional"))
      (node (ref "U7_MUX") (pin "2") (pinfunction "2Y2_2") (pintype "bidirectional"))
    )
    (net (code "112") (name "RS485_10_RX") (class "Default")
      (node (ref "RS_TRANS_8") (pin "RO") (pinfunction "R0_RO") (pintype "bidirectional"))
      (node (ref "U5_MUX") (pin "15") (pinfunction "1Y2_15") (pintype "bidirectional"))
    )
    (net (code "113") (name "RS485_10_TX") (class "Default")
      (node (ref "RS_TRANS_8") (pin "DI") (pinfunction "DI_DI") (pintype "bidirectional"))
      (node (ref "U5_MUX") (pin "2") (pinfunction "2Y2_2") (pintype "bidirectional"))
    )
    (net (code "114") (name "RS485_11_RX") (class "Default")
      (node (ref "RS_TRANS_10") (pin "RO") (pinfunction "R0_RO") (pintype "bidirectional"))
      (node (ref "U4_MUX") (pin "15") (pinfunction "1Y2_15") (pintype "bidirectional"))
    )
    (net (code "115") (name "RS485_11_TX") (class "Default")
      (node (ref "RS_TRANS_10") (pin "DI") (pinfunction "DI_DI") (pintype "bidirectional"))
      (node (ref "U4_MUX") (pin "2") (pinfunction "2Y2_2") (pintype "bidirectional"))
    )
    (net (code "116") (name "RS485_12_RX") (class "Default")
      (node (ref "RS_TRANS_12") (pin "RO") (pinfunction "R0_RO") (pintype "bidirectional"))
      (node (ref "U3_MUX") (pin "15") (pinfunction "1Y2_15") (pintype "bidirectional"))
    )
    (net (code "117") (name "RS485_12_TX") (class "Default")
      (node (ref "RS_TRANS_12") (pin "DI") (pinfunction "DI_DI") (pintype "bidirectional"))
      (node (ref "U3_MUX") (pin "2") (pinfunction "2Y2_2") (pintype "bidirectional"))
    )
    (net (code "118") (name "RS485_13_RX") (class "Default")
      (node (ref "RS_TRANS_13") (pin "RO") (pinfunction "R0_RO") (pintype "bidirectional"))
      (node (ref "U6_MUX") (pin "12") (pinfunction "1Y0_12") (pintype "bidirectional"))
    )
    (net (code "119") (name "RS485_13_TX") (class "Default")
      (node (ref "RS_TRANS_13") (pin "DI") (pinfunction "DI_DI") (pintype "bidirectional"))
      (node (ref "U6_MUX") (pin "1") (pinfunction "2Y0_1") (pintype "bidirectional"))
    )
    (net (code "120") (name "RS485_14_RX") (class "Default")
      (node (ref "RS_TRANS_14") (pin "RO") (pinfunction "R0_RO") (pintype "bidirectional"))
      (node (ref "U6_MUX") (pin "14") (pinfunction "1Y1_14") (pintype "bidirectional"))
    )
    (net (code "121") (name "RS485_14_TX") (class "Default")
      (node (ref "RS_TRANS_14") (pin "DI") (pinfunction "DI_DI") (pintype "bidirectional"))
      (node (ref "U6_MUX") (pin "5") (pinfunction "2Y1_5") (pintype "bidirectional"))
    )
    (net (code "122") (name "RS485_15_RX") (class "Default")
      (node (ref "RS_TRANS_15") (pin "RO") (pinfunction "R0_RO") (pintype "bidirectional"))
      (node (ref "U6_MUX") (pin "15") (pinfunction "1Y2_15") (pintype "bidirectional"))
    )
    (net (code "123") (name "RS485_15_TX") (class "Default")
      (node (ref "RS_TRANS_15") (pin "DI") (pinfunction "DI_DI") (pintype "bidirectional"))
      (node (ref "U6_MUX") (pin "2") (pinfunction "2Y2_2") (pintype "bidirectional"))
    )
    (net (code "124") (name "RS485_16_RX") (class "Default")
      (node (ref "RS_TRANS_16") (pin "RO") (pinfunction "R0_RO") (pintype "bidirectional"))
      (node (ref "U6_MUX") (pin "11") (pinfunction "1Y3_11") (pintype "bidirectional"))
    )
    (net (code "125") (name "RS485_16_TX") (class "Default")
      (node (ref "RS_TRANS_16") (pin "DI") (pinfunction "DI_DI") (pintype "bidirectional"))
      (node (ref "U6_MUX") (pin "4") (pinfunction "2Y3_4") (pintype "bidirectional"))
    )
    (net (code "126") (name "RS485_17_RX") (class "Default")
      (node (ref "RS_TRANS_17") (pin "RO") (pinfunction "R0_RO") (pintype "bidirectional"))
      (node (ref "U7_MUX") (pin "11") (pinfunction "1Y3_11") (pintype "bidirectional"))
    )
    (net (code "127") (name "RS485_17_TX") (class "Default")
      (node (ref "RS_TRANS_17") (pin "DI") (pinfunction "DI_DI") (pintype "bidirectional"))
      (node (ref "U7_MUX") (pin "4") (pinfunction "2Y3_4") (pintype "bidirectional"))
    )
    (net (code "128") (name "RS485_18_RX") (class "Default")
      (node (ref "RS-485-2") (pin "RO") (pinfunction "R0_RO") (pintype "bidirectional"))
      (node (ref "U3_MUX") (pin "11") (pinfunction "1Y3_11") (pintype "bidirectional"))
    )
    (net (code "129") (name "RS485_18_TX") (class "Default")
      (node (ref "RS-485-2") (pin "DI") (pinfunction "DI_DI") (pintype "bidirectional"))
      (node (ref "U3_MUX") (pin "4") (pinfunction "2Y3_4") (pintype "bidirectional"))
    )
    (net (code "130") (name "U2RX") (class "Default")
      (node (ref "U$5") (pin "P33") (pinfunction "PA6_P33") (pintype "bidirectional"))
      (node (ref "U2") (pin "3") (pinfunction "PD1(TXD)_3") (pintype "bidirectional"))
    )
    (net (code "131") (name "U2TX") (class "Default")
      (node (ref "U$5") (pin "P57") (pinfunction "PA7_P57") (pintype "bidirectional"))
      (node (ref "U2") (pin "2") (pinfunction "PD0(RXD)_2") (pintype "bidirectional"))
    )
    (net (code "132") (name "U3RX") (class "Default")
      (node (ref "U$5") (pin "P12") (pinfunction "PA4_P12") (pintype "bidirectional"))
      (node (ref "U3_MUX") (pin "13") (pinfunction "1Z_13") (pintype "bidirectional"))
    )
    (net (code "133") (name "U3TX") (class "Default")
      (node (ref "U$5") (pin "P11") (pinfunction "PA5_P11") (pintype "bidirectional"))
      (node (ref "U3_MUX") (pin "3") (pinfunction "2Z_3") (pintype "bidirectional"))
    )
    (net (code "134") (name "U3_MUX_S0") (class "Default")
      (node (ref "U$5") (pin "P44") (pinfunction "PH0_P44") (pintype "bidirectional"))
      (node (ref "U3_MUX") (pin "10") (pinfunction "S0_10") (pintype "input"))
    )
    (net (code "135") (name "U3_MUX_S1") (class "Default")
      (node (ref "U$5") (pin "P43") (pinfunction "PH1_P43") (pintype "bidirectional"))
      (node (ref "U3_MUX") (pin "9") (pinfunction "S1_9") (pintype "input"))
    )
    (net (code "136") (name "U4RX") (class "Default")
      (node (ref "U$5") (pin "P16") (pinfunction "PK0_P16") (pintype "bidirectional"))
      (node (ref "U4_MUX") (pin "13") (pinfunction "1Z_13") (pintype "bidirectional"))
    )
    (net (code "137") (name "U4TX") (class "Default")
      (node (ref "U$5") (pin "P15") (pinfunction "PK1_P15") (pintype "bidirectional"))
      (node (ref "U4_MUX") (pin "3") (pinfunction "2Z_3") (pintype "bidirectional"))
    )
    (net (code "138") (name "U4_MUX_S0") (class "Default")
      (node (ref "U$5") (pin "P51") (pinfunction "PM6_P51") (pintype "bidirectional"))
      (node (ref "U4_MUX") (pin "10") (pinfunction "S0_10") (pintype "input"))
    )
    (net (code "139") (name "U4_MUX_S1") (class "Default")
      (node (ref "U$5") (pin "P59") (pinfunction "PM7_P59") (pintype "bidirectional"))
      (node (ref "U4_MUX") (pin "9") (pinfunction "S1_9") (pintype "input"))
    )
    (net (code "140") (name "U5RX") (class "Default")
      (node (ref "U$5") (pin "P26") (pinfunction "PC6_P26") (pintype "bidirectional"))
      (node (ref "U5_MUX") (pin "13") (pinfunction "1Z_13") (pintype "bidirectional"))
    )
    (net (code "141") (name "U5TX") (class "Default")
      (node (ref "U$5") (pin "P23") (pinfunction "PC7_P23") (pintype "bidirectional"))
      (node (ref "U5_MUX") (pin "3") (pinfunction "2Z_3") (pintype "bidirectional"))
    )
    (net (code "142") (name "U5_MUX_S0") (class "Default")
      (node (ref "U$5") (pin "P64") (pinfunction "PL0_P64") (pintype "bidirectional"))
      (node (ref "U5_MUX") (pin "10") (pinfunction "S0_10") (pintype "input"))
    )
    (net (code "143") (name "U5_MUX_S1") (class "Default")
      (node (ref "U$5") (pin "P63") (pinfunction "PL1_P63") (pintype "bidirectional"))
      (node (ref "U5_MUX") (pin "9") (pinfunction "S1_9") (pintype "input"))
    )
    (net (code "144") (name "U6RX") (class "Default")
      (node (ref "U$5") (pin "P8") (pinfunction "PP0_P8") (pintype "bidirectional"))
      (node (ref "U6_MUX") (pin "13") (pinfunction "1Z_13") (pintype "bidirectional"))
    )
    (net (code "145") (name "U6TX") (class "Default")
      (node (ref "U$5") (pin "P7") (pinfunction "PP1_P7") (pintype "bidirectional"))
      (node (ref "U6_MUX") (pin "3") (pinfunction "2Z_3") (pintype "bidirectional"))
    )
    (net (code "146") (name "U6_MUX_S0") (class "Default")
      (node (ref "U$5") (pin "P14") (pinfunction "PK2_P14") (pintype "bidirectional"))
      (node (ref "U6_MUX") (pin "10") (pinfunction "S0_10") (pintype "input"))
    )
    (net (code "147") (name "U6_MUX_S1") (class "Default")
      (node (ref "U$5") (pin "P13") (pinfunction "PK3_P13") (pintype "bidirectional"))
      (node (ref "U6_MUX") (pin "9") (pinfunction "S1_9") (pintype "input"))
    )
    (net (code "148") (name "U7RX") (class "Default")
      (node (ref "U$5") (pin "P28") (pinfunction "PC4_P28") (pintype "bidirectional"))
      (node (ref "U7_MUX") (pin "13") (pinfunction "1Z_13") (pintype "bidirectional"))
    )
    (net (code "149") (name "U7TX") (class "Default")
      (node (ref "U$5") (pin "P27") (pinfunction "PC5_P27") (pintype "bidirectional"))
      (node (ref "U7_MUX") (pin "3") (pinfunction "2Z_3") (pintype "bidirectional"))
    )
    (net (code "150") (name "U7_MUX_S0") (class "Default")
      (node (ref "U$5") (pin "P38") (pinfunction "PE0_P38") (pintype "bidirectional"))
      (node (ref "U7_MUX") (pin "10") (pinfunction "S0_10") (pintype "input"))
    )
    (net (code "151") (name "U7_MUX_S1") (class "Default")
      (node (ref "U$5") (pin "P37") (pinfunction "PE1_P37") (pintype "bidirectional"))
      (node (ref "U7_MUX") (pin "9") (pinfunction "S1_9") (pintype "input"))
    )
    (net (code "152") (name "unconnected-(FAN1-Pad3)") (class "Default")
      (node (ref "FAN1") (pin "3") (pinfunction "3_3") (pintype "passive"))
    )
    (net (code "153") (name "unconnected-(FAN2-Pad3)") (class "Default")
      (node (ref "FAN2") (pin "3") (pinfunction "3_3") (pintype "passive"))
    )
    (net (code "154") (name "unconnected-(FAN3-Pad3)") (class "Default")
      (node (ref "FAN3") (pin "3") (pinfunction "3_3") (pintype "passive"))
    )
    (net (code "155") (name "unconnected-(FAN4-Pad3)") (class "Default")
      (node (ref "FAN4") (pin "3") (pinfunction "3_3") (pintype "passive"))
    )
    (net (code "156") (name "unconnected-(GPS-1PPS-PadP$13)") (class "Default")
      (node (ref "GPS") (pin "P$13") (pinfunction "1PPS_P$13") (pintype "bidirectional"))
    )
    (net (code "157") (name "unconnected-(GPS-NC-PadP$6)") (class "Default")
      (node (ref "GPS") (pin "P$6") (pinfunction "NC_P$6") (pintype "bidirectional"))
    )
    (net (code "158") (name "unconnected-(GPS-NC-PadP$7)") (class "Default")
      (node (ref "GPS") (pin "P$7") (pinfunction "NC_P$7") (pintype "bidirectional"))
    )
    (net (code "159") (name "unconnected-(GPS-NC-PadP$15)") (class "Default")
      (node (ref "GPS") (pin "P$15") (pinfunction "NC_P$15") (pintype "bidirectional"))
    )
    (net (code "160") (name "unconnected-(GPS-NC-PadP$16)") (class "Default")
      (node (ref "GPS") (pin "P$16") (pinfunction "NC_P$16") (pintype "bidirectional"))
    )
    (net (code "161") (name "unconnected-(GPS-NC-PadP$17)") (class "Default")
      (node (ref "GPS") (pin "P$17") (pinfunction "NC_P$17") (pintype "bidirectional"))
    )
    (net (code "162") (name "unconnected-(GPS-NC-PadP$18)") (class "Default")
      (node (ref "GPS") (pin "P$18") (pinfunction "NC_P$18") (pintype "bidirectional"))
    )
    (net (code "163") (name "unconnected-(GPS-NC-PadP$20)") (class "Default")
      (node (ref "GPS") (pin "P$20") (pinfunction "NC_P$20") (pintype "bidirectional"))
    )
    (net (code "164") (name "unconnected-(GPS-NRESET-PadP$2)") (class "Default")
      (node (ref "GPS") (pin "P$2") (pinfunction "NRESET_P$2") (pintype "bidirectional"))
    )
    (net (code "165") (name "unconnected-(GPS-RTCM-PadP$14)") (class "Default")
      (node (ref "GPS") (pin "P$14") (pinfunction "RTCM_P$14") (pintype "bidirectional"))
    )
    (net (code "166") (name "unconnected-(GPS-VBACKUP-PadP$4)") (class "Default")
      (node (ref "GPS") (pin "P$4") (pinfunction "VBACKUP_P$4") (pintype "bidirectional"))
    )
    (net (code "167") (name "unconnected-(H1-Pad1)") (class "Default")
      (node (ref "H1") (pin "1") (pinfunction "1_1") (pintype "passive"))
    )
    (net (code "168") (name "unconnected-(H2-Pad1)") (class "Default")
      (node (ref "H2") (pin "1") (pinfunction "1_1") (pintype "passive"))
    )
    (net (code "169") (name "unconnected-(H3-Pad1)") (class "Default")
      (node (ref "H3") (pin "1") (pinfunction "1_1") (pintype "passive"))
    )
    (net (code "170") (name "unconnected-(H4-Pad1)") (class "Default")
      (node (ref "H4") (pin "1") (pinfunction "1_1") (pintype "passive"))
    )
    (net (code "171") (name "unconnected-(U$1-4-Pad3.3V)") (class "Default")
      (node (ref "U$1") (pin "3.3V") (pinfunction "4_3.3V") (pintype "bidirectional"))
    )
    (net (code "172") (name "unconnected-(U$2-Pad4)") (class "Default")
      (node (ref "U$2") (pin "4") (pinfunction "4_4") (pintype "bidirectional"))
    )
    (net (code "173") (name "unconnected-(U$2-Pad5)") (class "Default")
      (node (ref "U$2") (pin "5") (pinfunction "5_5") (pintype "bidirectional"))
    )
    (net (code "174") (name "unconnected-(U$2-Pad7)") (class "Default")
      (node (ref "U$2") (pin "7") (pinfunction "7_7") (pintype "bidirectional"))
    )
    (net (code "175") (name "unconnected-(U$2-Pad8)") (class "Default")
      (node (ref "U$2") (pin "8") (pinfunction "8_8") (pintype "bidirectional"))
    )
    (net (code "176") (name "unconnected-(U$5-PA2{slash}PQ3-PadP54)") (class "Default")
      (node (ref "U$5") (pin "P54") (pinfunction "PA2/PQ3_P54") (pintype "bidirectional"))
    )
    (net (code "177") (name "unconnected-(U$5-PA3{slash}PQ2-PadP55)") (class "Default")
      (node (ref "U$5") (pin "P55") (pinfunction "PA3/PQ2_P55") (pintype "bidirectional"))
    )
    (net (code "178") (name "unconnected-(U$5-PB2-PadP22)") (class "Default")
      (node (ref "U$5") (pin "P22") (pinfunction "PB2_P22") (pintype "bidirectional"))
    )
    (net (code "179") (name "unconnected-(U$5-PB3-PadP21)") (class "Default")
      (node (ref "U$5") (pin "P21") (pinfunction "PB3_P21") (pintype "bidirectional"))
    )
    (net (code "180") (name "unconnected-(U$5-PB4-PadP18)") (class "Default")
      (node (ref "U$5") (pin "P18") (pinfunction "PB4_P18") (pintype "bidirectional"))
    )
    (net (code "181") (name "unconnected-(U$5-PB5-PadP17)") (class "Default")
      (node (ref "U$5") (pin "P17") (pinfunction "PB5_P17") (pintype "bidirectional"))
    )
    (net (code "182") (name "unconnected-(U$5-PD0-PadP74)") (class "Default")
      (node (ref "U$5") (pin "P74") (pinfunction "PD0_P74") (pintype "bidirectional"))
    )
    (net (code "183") (name "unconnected-(U$5-PD1-PadP75)") (class "Default")
      (node (ref "U$5") (pin "P75") (pinfunction "PD1_P75") (pintype "bidirectional"))
    )
    (net (code "184") (name "unconnected-(U$5-PD2-PadP9)") (class "Default")
      (node (ref "U$5") (pin "P9") (pinfunction "PD2_P9") (pintype "bidirectional"))
    )
    (net (code "185") (name "unconnected-(U$5-PD3-PadP24)") (class "Default")
      (node (ref "U$5") (pin "P24") (pinfunction "PD3_P24") (pintype "bidirectional"))
    )
    (net (code "186") (name "unconnected-(U$5-PD7-PadP34)") (class "Default")
      (node (ref "U$5") (pin "P34") (pinfunction "PD7_P34") (pintype "bidirectional"))
    )
    (net (code "187") (name "unconnected-(U$5-PE2-PadP36)") (class "Default")
      (node (ref "U$5") (pin "P36") (pinfunction "PE2_P36") (pintype "bidirectional"))
    )
    (net (code "188") (name "unconnected-(U$5-PE3-PadP35)") (class "Default")
      (node (ref "U$5") (pin "P35") (pinfunction "PE3_P35") (pintype "bidirectional"))
    )
    (net (code "189") (name "unconnected-(U$5-PE4-PadP29)") (class "Default")
      (node (ref "U$5") (pin "P29") (pinfunction "PE4_P29") (pintype "bidirectional"))
    )
    (net (code "190") (name "unconnected-(U$5-PE5-PadP25)") (class "Default")
      (node (ref "U$5") (pin "P25") (pinfunction "PE5_P25") (pintype "bidirectional"))
    )
    (net (code "191") (name "unconnected-(U$5-PF1-PadP70)") (class "Default")
      (node (ref "U$5") (pin "P70") (pinfunction "PF1_P70") (pintype "bidirectional"))
    )
    (net (code "192") (name "unconnected-(U$5-PF2-PadP69)") (class "Default")
      (node (ref "U$5") (pin "P69") (pinfunction "PF2_P69") (pintype "bidirectional"))
    )
    (net (code "193") (name "unconnected-(U$5-PF3-PadP68)") (class "Default")
      (node (ref "U$5") (pin "P68") (pinfunction "PF3_P68") (pintype "bidirectional"))
    )
    (net (code "194") (name "unconnected-(U$5-PG0-PadP67)") (class "Default")
      (node (ref "U$5") (pin "P67") (pinfunction "PG0_P67") (pintype "bidirectional"))
    )
    (net (code "195") (name "unconnected-(U$5-PG1-PadP50)") (class "Default")
      (node (ref "U$5") (pin "P50") (pinfunction "PG1_P50") (pintype "bidirectional"))
    )
    (net (code "196") (name "unconnected-(U$5-PH2-PadP78)") (class "Default")
      (node (ref "U$5") (pin "P78") (pinfunction "PH2_P78") (pintype "bidirectional"))
    )
    (net (code "197") (name "unconnected-(U$5-PH3-PadP77)") (class "Default")
      (node (ref "U$5") (pin "P77") (pinfunction "PH3_P77") (pintype "bidirectional"))
    )
    (net (code "198") (name "unconnected-(U$5-PK4-PadP49)") (class "Default")
      (node (ref "U$5") (pin "P49") (pinfunction "PK4_P49") (pintype "bidirectional"))
    )
    (net (code "199") (name "unconnected-(U$5-PK5-PadP48)") (class "Default")
      (node (ref "U$5") (pin "P48") (pinfunction "PK5_P48") (pintype "bidirectional"))
    )
    (net (code "200") (name "unconnected-(U$5-PK6-PadP42)") (class "Default")
      (node (ref "U$5") (pin "P42") (pinfunction "PK6_P42") (pintype "bidirectional"))
    )
    (net (code "201") (name "unconnected-(U$5-PK7-PadP41)") (class "Default")
      (node (ref "U$5") (pin "P41") (pinfunction "PK7_P41") (pintype "bidirectional"))
    )
    (net (code "202") (name "unconnected-(U$5-PL2-PadP62)") (class "Default")
      (node (ref "U$5") (pin "P62") (pinfunction "PL2_P62") (pintype "bidirectional"))
    )
    (net (code "203") (name "unconnected-(U$5-PL3-PadP61)") (class "Default")
      (node (ref "U$5") (pin "P61") (pinfunction "PL3_P61") (pintype "bidirectional"))
    )
    (net (code "204") (name "unconnected-(U$5-PL4-PadP66)") (class "Default")
      (node (ref "U$5") (pin "P66") (pinfunction "PL4_P66") (pintype "bidirectional"))
    )
    (net (code "205") (name "unconnected-(U$5-PL5-PadP65)") (class "Default")
      (node (ref "U$5") (pin "P65") (pinfunction "PL5_P65") (pintype "bidirectional"))
    )
    (net (code "206") (name "unconnected-(U$5-PM0-PadP47)") (class "Default")
      (node (ref "U$5") (pin "P47") (pinfunction "PM0_P47") (pintype "bidirectional"))
    )
    (net (code "207") (name "unconnected-(U$5-PM1-PadP46)") (class "Default")
      (node (ref "U$5") (pin "P46") (pinfunction "PM1_P46") (pintype "bidirectional"))
    )
    (net (code "208") (name "unconnected-(U$5-PM2-PadP45)") (class "Default")
      (node (ref "U$5") (pin "P45") (pinfunction "PM2_P45") (pintype "bidirectional"))
    )
    (net (code "209") (name "unconnected-(U$5-PM3-PadP79)") (class "Default")
      (node (ref "U$5") (pin "P79") (pinfunction "PM3_P79") (pintype "bidirectional"))
    )
    (net (code "210") (name "unconnected-(U$5-PM4-PadP32)") (class "Default")
      (node (ref "U$5") (pin "P32") (pinfunction "PM4_P32") (pintype "bidirectional"))
    )
    (net (code "211") (name "unconnected-(U$5-PM5-PadP31)") (class "Default")
      (node (ref "U$5") (pin "P31") (pinfunction "PM5_P31") (pintype "bidirectional"))
    )
    (net (code "212") (name "unconnected-(U$5-PN2-PadP73)") (class "Default")
      (node (ref "U$5") (pin "P73") (pinfunction "PN2_P73") (pintype "bidirectional"))
    )
    (net (code "213") (name "unconnected-(U$5-PN3-PadP72)") (class "Default")
      (node (ref "U$5") (pin "P72") (pinfunction "PN3_P72") (pintype "bidirectional"))
    )
    (net (code "214") (name "unconnected-(U$5-PN4-PadP1)") (class "Default")
      (node (ref "U$5") (pin "P1") (pinfunction "PN4_P1") (pintype "bidirectional"))
    )
    (net (code "215") (name "unconnected-(U$5-PN5-PadP2)") (class "Default")
      (node (ref "U$5") (pin "P2") (pinfunction "PN5_P2") (pintype "bidirectional"))
    )
    (net (code "216") (name "unconnected-(U$5-PP2-PadP71)") (class "Default")
      (node (ref "U$5") (pin "P71") (pinfunction "PP2_P71") (pintype "bidirectional"))
    )
    (net (code "217") (name "unconnected-(U$5-PP3-PadP53)") (class "Default")
      (node (ref "U$5") (pin "P53") (pinfunction "PP3_P53") (pintype "bidirectional"))
    )
    (net (code "218") (name "unconnected-(U$5-PP5-PadP58)") (class "Default")
      (node (ref "U$5") (pin "P58") (pinfunction "PP5_P58") (pintype "bidirectional"))
    )
    (net (code "219") (name "unconnected-(U$5-PQ0-PadP4)") (class "Default")
      (node (ref "U$5") (pin "P4") (pinfunction "PQ0_P4") (pintype "bidirectional"))
    )
    (net (code "220") (name "unconnected-(U$5-PQ1-PadP52)") (class "Default")
      (node (ref "U$5") (pin "P52") (pinfunction "PQ1_P52") (pintype "bidirectional"))
    )
    (net (code "221") (name "unconnected-(U$5-RST_1-PadP76)") (class "Default")
      (node (ref "U$5") (pin "P76") (pinfunction "RST_1_P76") (pintype "bidirectional"))
    )
    (net (code "222") (name "unconnected-(U$5-RST_2-PadP56)") (class "Default")
      (node (ref "U$5") (pin "P56") (pinfunction "RST_2_P56") (pintype "bidirectional"))
    )
    (net (code "223") (name "unconnected-(U2-PB0(ICP)-Pad14)") (class "Default")
      (node (ref "U2") (pin "14") (pinfunction "PB0(ICP)_14") (pintype "bidirectional"))
    )
    (net (code "224") (name "unconnected-(U2-PB1(OC1A)-Pad15)") (class "Default")
      (node (ref "U2") (pin "15") (pinfunction "PB1(OC1A)_15") (pintype "bidirectional"))
    )
    (net (code "225") (name "unconnected-(U2-PB2(SS{slash}OC1B)-Pad16)") (class "Default")
      (node (ref "U2") (pin "16") (pinfunction "PB2(SS/OC1B)_16") (pintype "bidirectional"))
    )
    (net (code "226") (name "unconnected-(U2-PC0(ADC0)-Pad23)") (class "Default")
      (node (ref "U2") (pin "23") (pinfunction "PC0(ADC0)_23") (pintype "bidirectional"))
    )
    (net (code "227") (name "unconnected-(U2-PC1(ADC1)-Pad24)") (class "Default")
      (node (ref "U2") (pin "24") (pinfunction "PC1(ADC1)_24") (pintype "bidirectional"))
    )
    (net (code "228") (name "unconnected-(U2-PC2(ADC2)-Pad25)") (class "Default")
      (node (ref "U2") (pin "25") (pinfunction "PC2(ADC2)_25") (pintype "bidirectional"))
    )
    (net (code "229") (name "unconnected-(U2-PC3(ADC3)-Pad26)") (class "Default")
      (node (ref "U2") (pin "26") (pinfunction "PC3(ADC3)_26") (pintype "bidirectional"))
    )
    (net (code "230") (name "unconnected-(U2-PD5(T1)-Pad11)") (class "Default")
      (node (ref "U2") (pin "11") (pinfunction "PD5(T1)_11") (pintype "bidirectional"))
    )
    (net (code "231") (name "unconnected-(U2-PD6(AIN0)-Pad12)") (class "Default")
      (node (ref "U2") (pin "12") (pinfunction "PD6(AIN0)_12") (pintype "bidirectional"))
    )
    (net (code "232") (name "unconnected-(U2-PD7(AIN1)-Pad13)") (class "Default")
      (node (ref "U2") (pin "13") (pinfunction "PD7(AIN1)_13") (pintype "bidirectional"))
    )
    (net (code "233") (name "unconnected-(U4_MUX-1Y3-Pad11)") (class "Default")
      (node (ref "U4_MUX") (pin "11") (pinfunction "1Y3_11") (pintype "bidirectional"))
    )
    (net (code "234") (name "unconnected-(U4_MUX-2Y3-Pad4)") (class "Default")
      (node (ref "U4_MUX") (pin "4") (pinfunction "2Y3_4") (pintype "bidirectional"))
    )
    (net (code "235") (name "unconnected-(U5_MUX-1Y3-Pad11)") (class "Default")
      (node (ref "U5_MUX") (pin "11") (pinfunction "1Y3_11") (pintype "bidirectional"))
    )
    (net (code "236") (name "unconnected-(U5_MUX-2Y3-Pad4)") (class "Default")
      (node (ref "U5_MUX") (pin "4") (pinfunction "2Y3_4") (pintype "bidirectional"))
    )
  )
)
